# RT_SUPER_B.net
KiCad netlist of a schematic drawn in Altium Designer
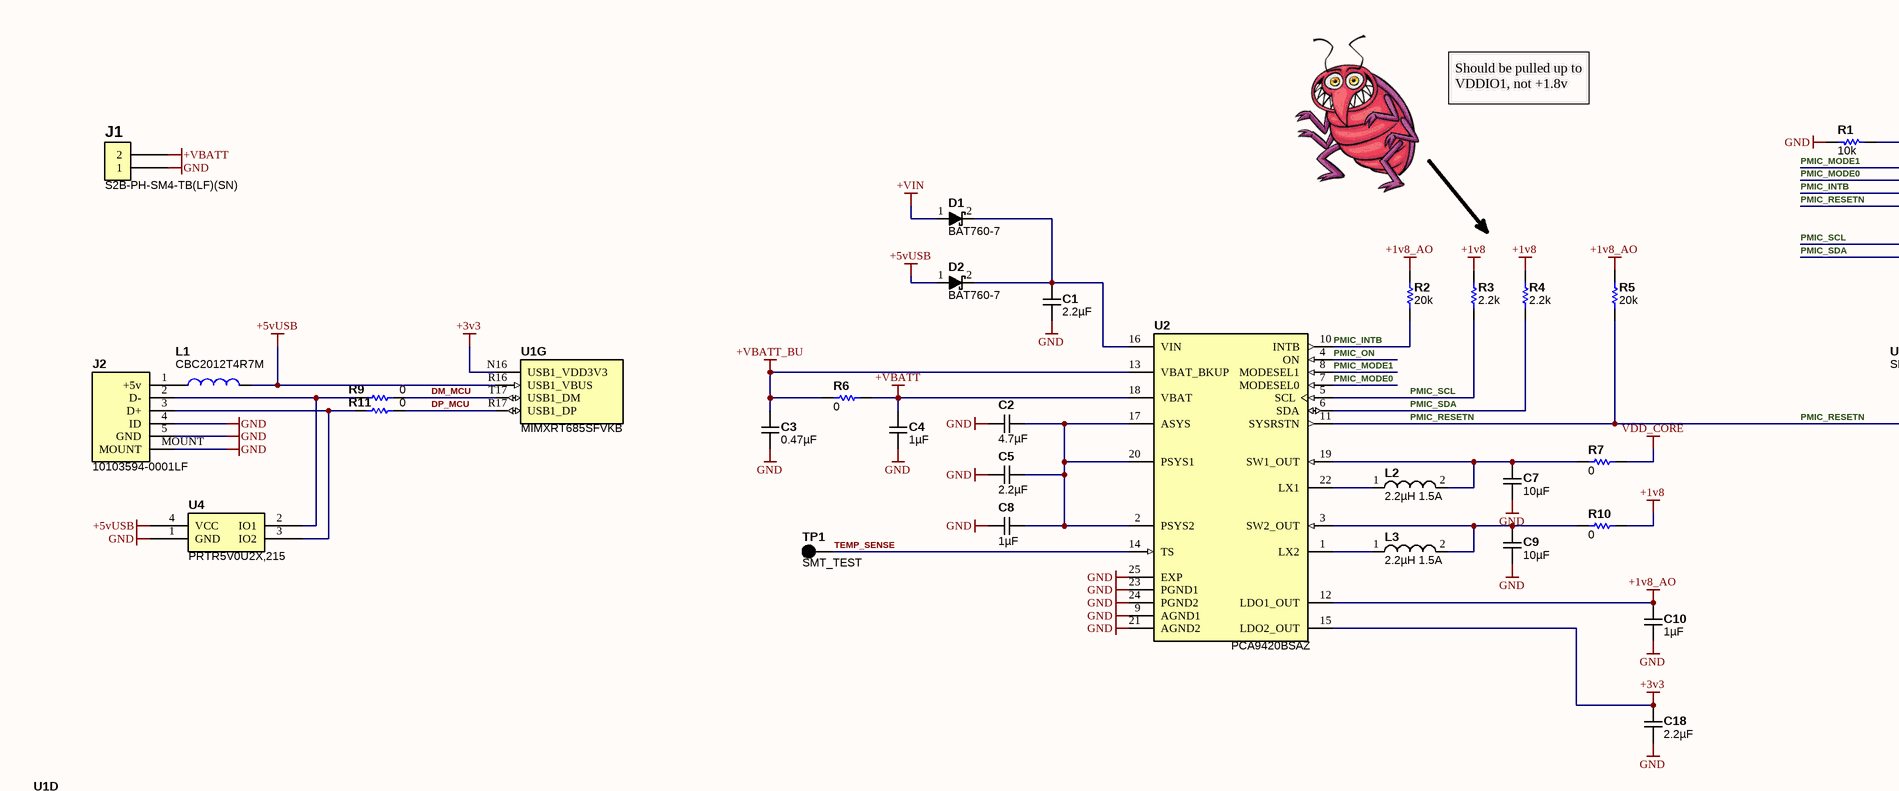
[diagram p0: RT_SUPER_B.SchDoc, top left]
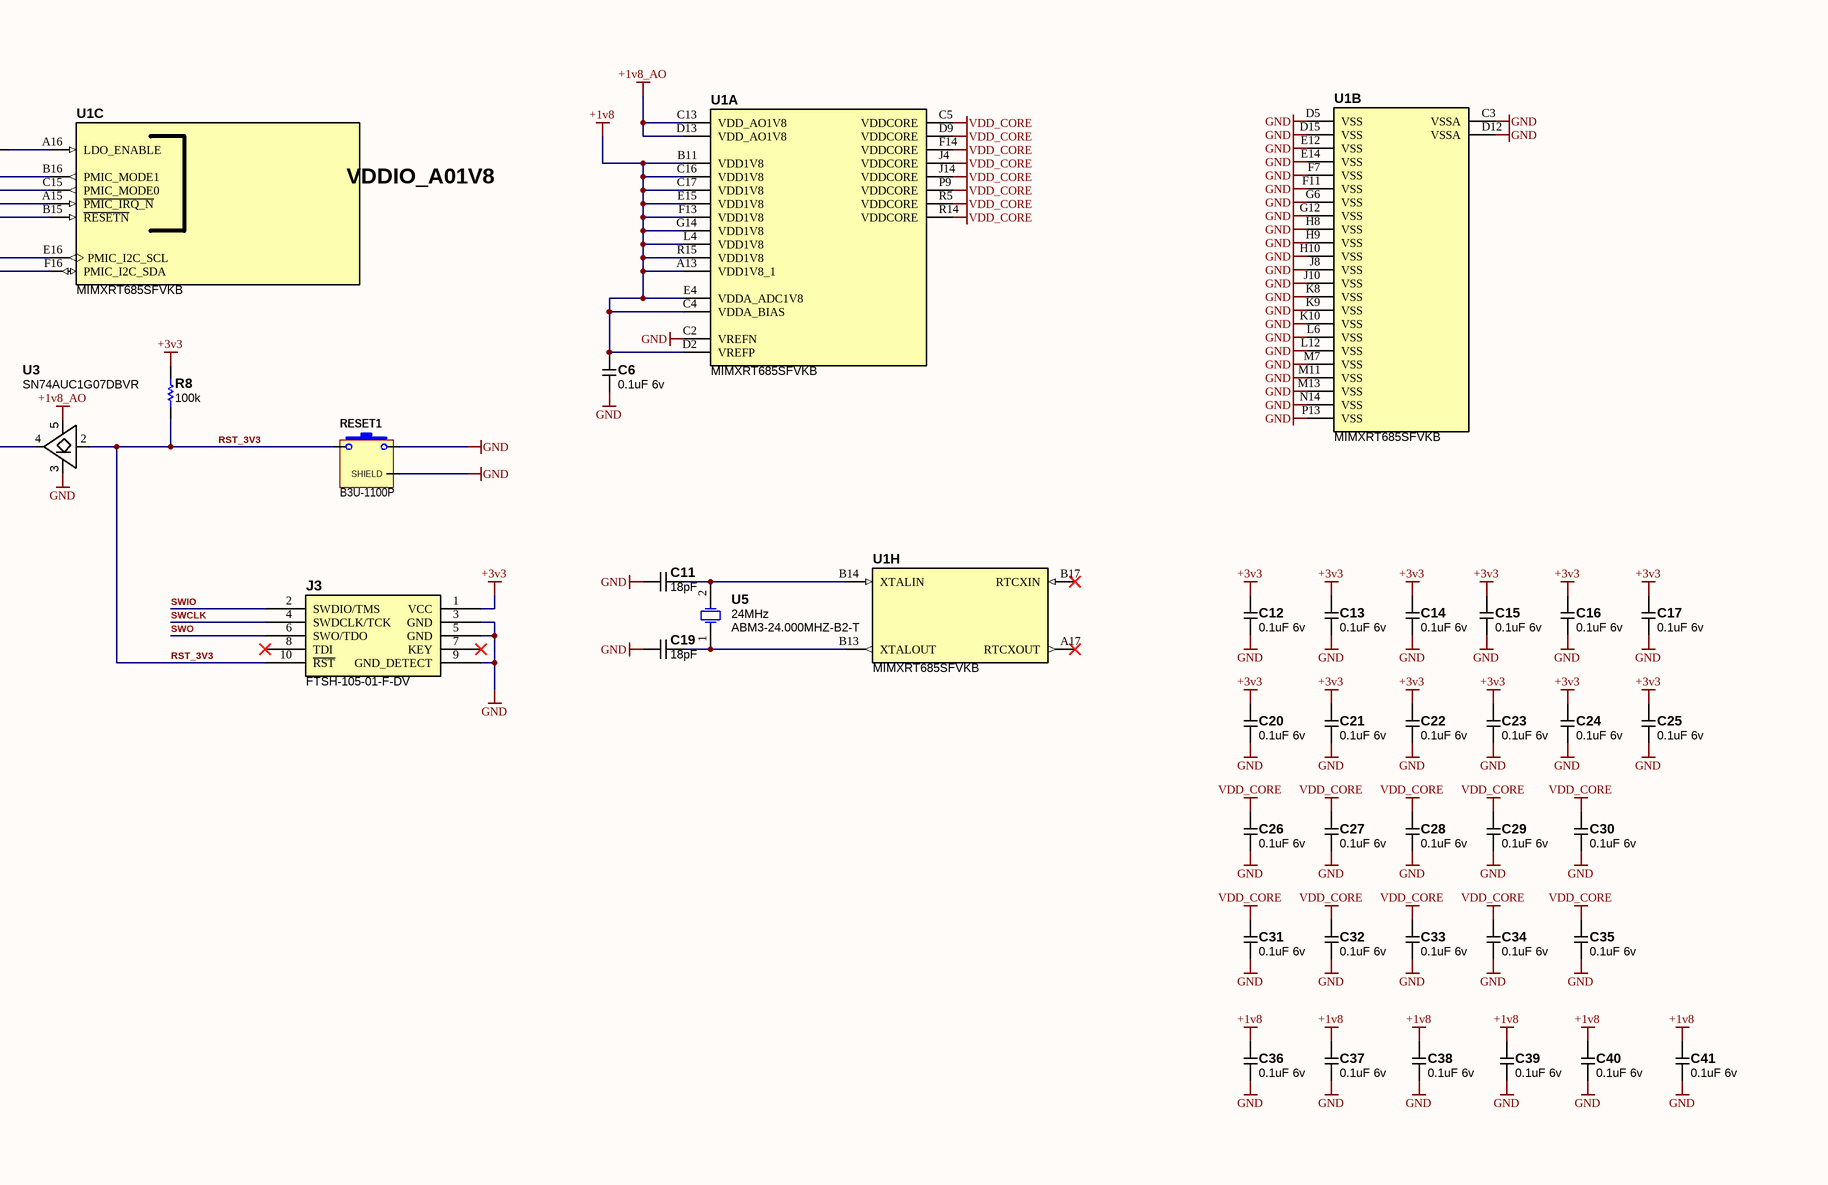
[diagram p1: RT_SUPER_B.SchDoc, top right]
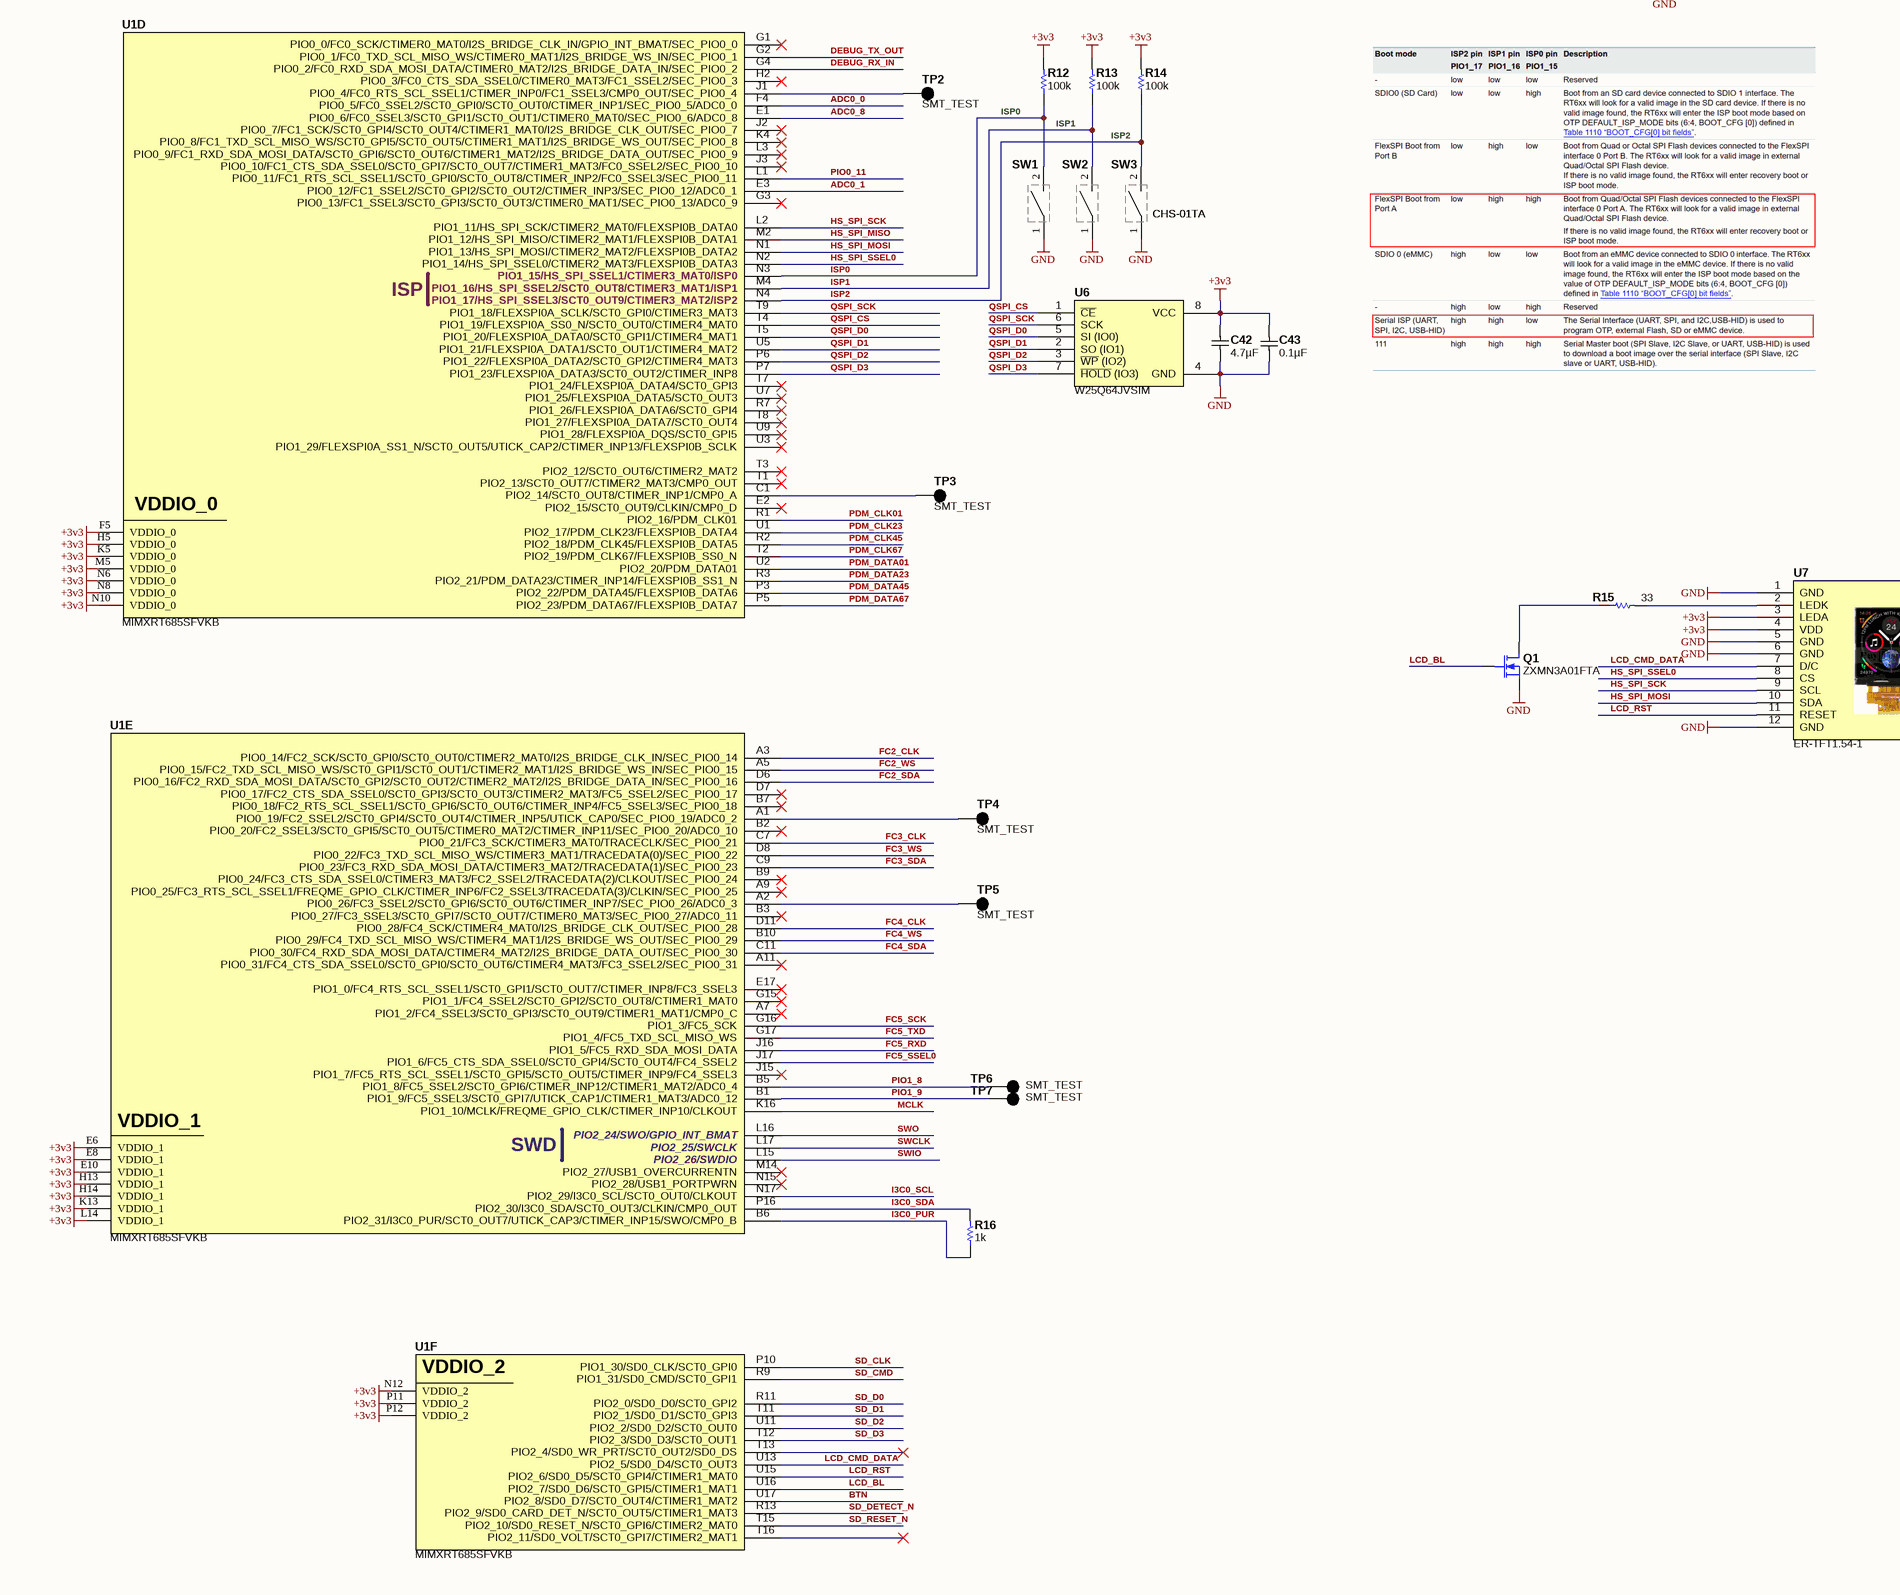
[diagram p2: RT_SUPER_B.SchDoc, bottom left]
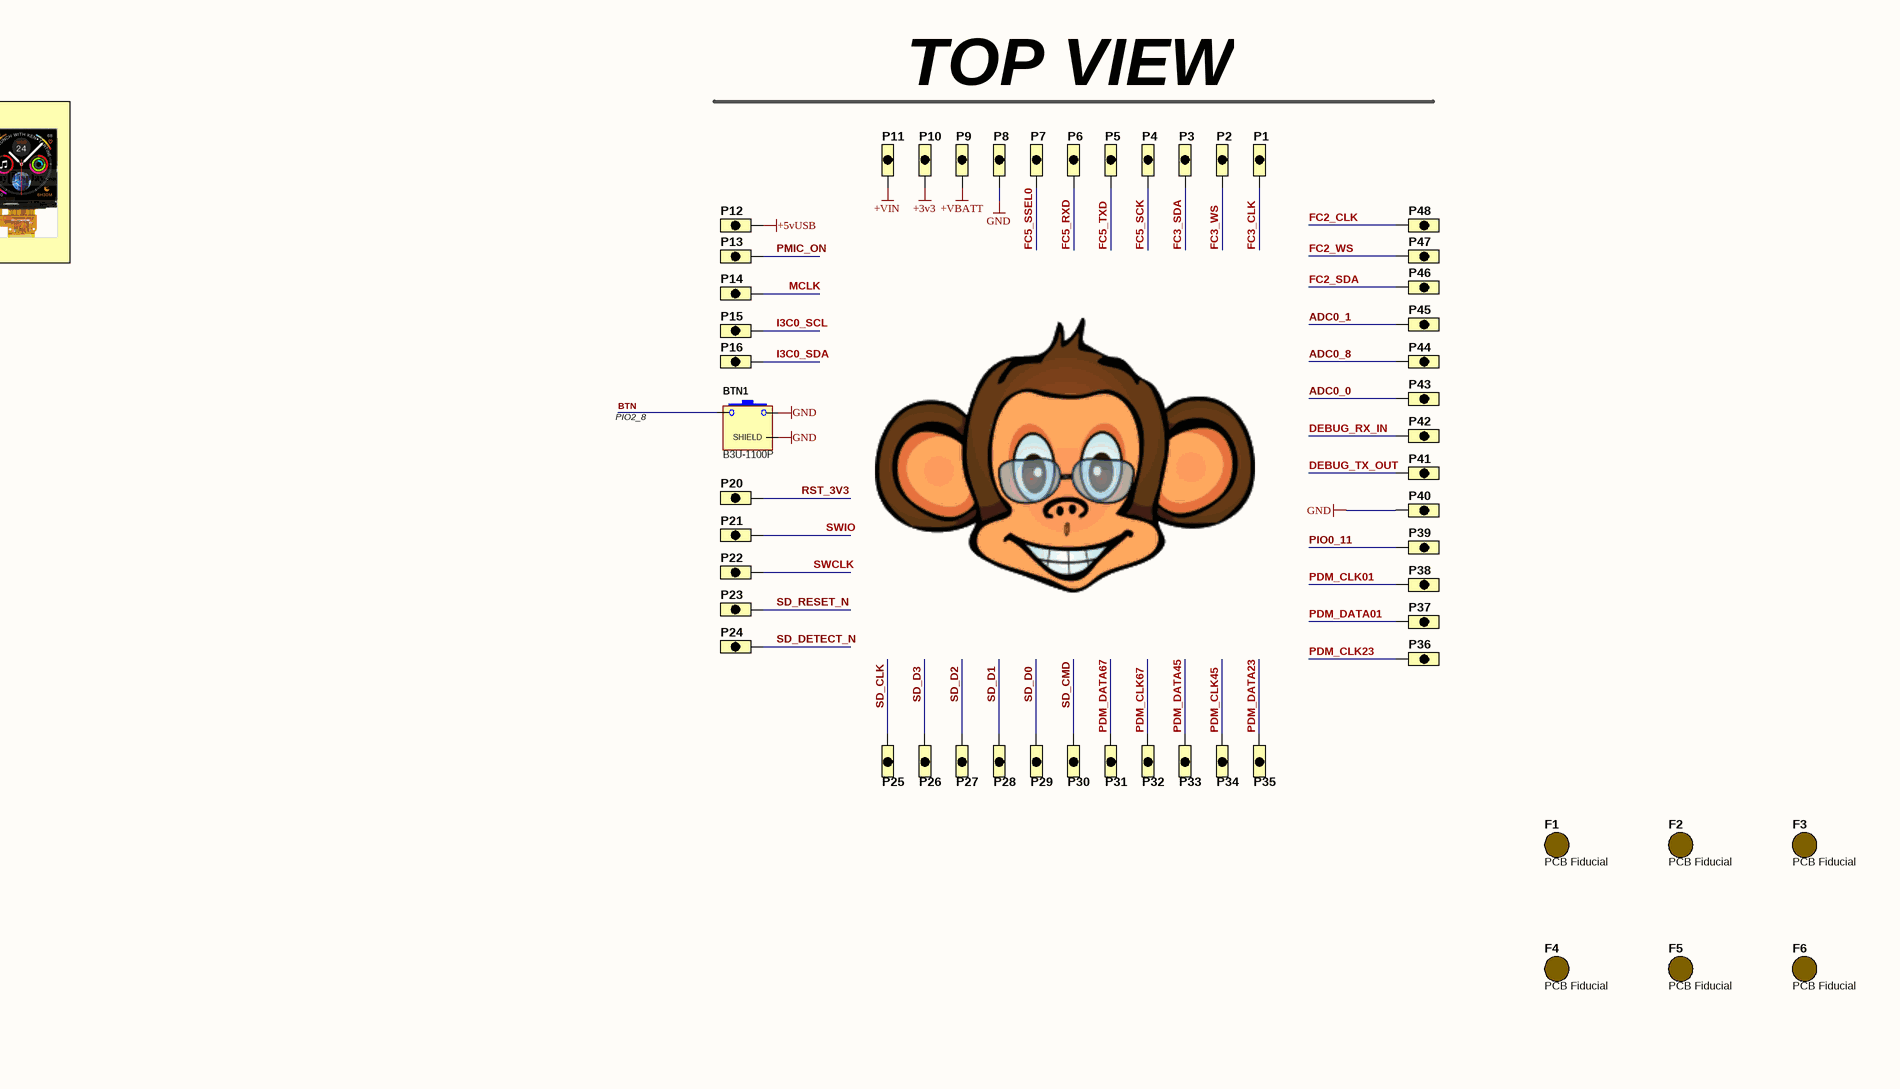
[diagram p3: RT_SUPER_B.SchDoc, bottom right]

(export (version "E")
  (design (tool "Eeschema 10.0.6"))
  (components
    (comp (ref "BTN1")
      (value "B3U-1100P")
      (footprint "OMRON_B3U-1100P")
      (description "SWITCH TACTILE SPST-NO 0.05A 12V")
      (fields (field (name "MANUFACTURER") "Omron Electronics Inc-EMC Div"))
      (libsource (lib "Switches-N") (part "B3U-1100P"))
    )
    (comp (ref "C1")
      (value "2.2µF")
      (footprint "C0603_0.90MM_MD")
      (description "CAP CER 2.2UF 6.3V X7R 0603")
      (fields
        (field (name "MANUFACTURER PART NUMBER") "GCM188R70J225KE22D")
        (field (name "MANUFACTURER") "Murata Electronics")
      )
      (libsource (lib "Capacitors - Murata - AEC-Q200") (part "C_2P_NP"))
    )
    (comp (ref "C2")
      (value "4.7µF")
      (footprint "C0603_1.00MM_MD")
      (description "CAP CER 4.7UF 6.3V X7S 0603")
      (fields
        (field (name "MANUFACTURER PART NUMBER") "GCJ188C70J475KE02D")
        (field (name "MANUFACTURER") "Murata Electronics")
      )
      (libsource (lib "Capacitors - Murata - AEC-Q200") (part "C_2P_NP"))
    )
    (comp (ref "C3")
      (value "0.47µF")
      (footprint "C0402_0.55MM_HD")
      (description "CAP CER 0.47UF 25V X5R 0402")
      (fields
        (field (name "MANUFACTURER PART NUMBER") "GRT155R61E474KE01D")
        (field (name "MANUFACTURER") "Murata Electronics")
      )
      (libsource (lib "Capacitors - Murata - AEC-Q200") (part "C_2P_NP"))
    )
    (comp (ref "C4")
      (value "1µF")
      (footprint "C0402_0.55MM_HD")
      (description "CAP CER 1UF 10V X7S 0402")
      (fields
        (field (name "MANUFACTURER PART NUMBER") "GCM155C71A105KE38D")
        (field (name "MANUFACTURER") "Murata Electronics")
      )
      (libsource (lib "Capacitors - Murata - AEC-Q200") (part "C_2P_NP"))
    )
    (comp (ref "C5")
      (value "2.2µF")
      (footprint "C0603_0.90MM_MD")
      (description "CAP CER 2.2UF 6.3V X7R 0603")
      (fields
        (field (name "MANUFACTURER PART NUMBER") "GCM188R70J225KE22D")
        (field (name "MANUFACTURER") "Murata Electronics")
      )
      (libsource (lib "Capacitors - Murata - AEC-Q200") (part "C_2P_NP"))
    )
    (comp (ref "C6")
      (value "0.1uF 6v")
      (footprint "C0201_PERFECT")
      (description "Cap Ceramic 0.1uF 6.3VDC X5R 10% SMD 0201 Paper T/R")
      (fields
        (field (name "MANUFACTURER PART NUMBER") "CC0201KRX5R5BB104")
        (field (name "MANUFACTURER") "Yageo")
      )
      (libsource (lib "eCapacitors") (part "CC0201KRX5R5BB104"))
    )
    (comp (ref "C7")
      (value "10µF")
      (footprint "C0603_0.90MM_MD")
      (description "CAP CER 10UF 10V X5R 0603")
      (fields
        (field (name "MANUFACTURER PART NUMBER") "GRT188R61A106ME13D")
        (field (name "MANUFACTURER") "Murata Electronics")
      )
      (libsource (lib "Capacitors - Murata - AEC-Q200") (part "C_2P_NP"))
    )
    (comp (ref "C8")
      (value "1µF")
      (footprint "C0402_0.55MM_HD")
      (description "CAP CER 1UF 10V X7S 0402")
      (fields
        (field (name "MANUFACTURER PART NUMBER") "GCM155C71A105KE38D")
        (field (name "MANUFACTURER") "Murata Electronics")
      )
      (libsource (lib "Capacitors - Murata - AEC-Q200") (part "C_2P_NP"))
    )
    (comp (ref "C9")
      (value "10µF")
      (footprint "C0603_0.90MM_MD")
      (description "CAP CER 10UF 10V X5R 0603")
      (fields
        (field (name "MANUFACTURER PART NUMBER") "GRT188R61A106ME13D")
        (field (name "MANUFACTURER") "Murata Electronics")
      )
      (libsource (lib "Capacitors - Murata - AEC-Q200") (part "C_2P_NP"))
    )
    (comp (ref "C10")
      (value "1µF")
      (footprint "C0402_0.55MM_HD")
      (description "CAP CER 1UF 10V X7S 0402")
      (fields
        (field (name "MANUFACTURER PART NUMBER") "GCM155C71A105KE38D")
        (field (name "MANUFACTURER") "Murata Electronics")
      )
      (libsource (lib "Capacitors - Murata - AEC-Q200") (part "C_2P_NP"))
    )
    (comp (ref "C11")
      (value "18pF")
      (footprint "C0402_0.55MM_HD")
      (description "CAP CER 18PF 50V C0G 0402")
      (fields
        (field (name "MANUFACTURER PART NUMBER") "CGA2B2C0G1H180J050BA")
        (field (name "MANUFACTURER") "TDK Corporation")
      )
      (libsource (lib "Capacitors - TDK- AEC-Q200") (part "C_2P_NP"))
    )
    (comp (ref "C12")
      (value "0.1uF 6v")
      (footprint "C0201_PERFECT")
      (description "Cap Ceramic 0.1uF 6.3VDC X5R 10% SMD 0201 Paper T/R")
      (fields
        (field (name "MANUFACTURER PART NUMBER") "CC0201KRX5R5BB104")
        (field (name "MANUFACTURER") "Yageo")
      )
      (libsource (lib "eCapacitors") (part "CC0201KRX5R5BB104"))
    )
    (comp (ref "C13")
      (value "0.1uF 6v")
      (footprint "C0201_PERFECT")
      (description "Cap Ceramic 0.1uF 6.3VDC X5R 10% SMD 0201 Paper T/R")
      (fields
        (field (name "MANUFACTURER PART NUMBER") "CC0201KRX5R5BB104")
        (field (name "MANUFACTURER") "Yageo")
      )
      (libsource (lib "eCapacitors") (part "CC0201KRX5R5BB104"))
    )
    (comp (ref "C14")
      (value "0.1uF 6v")
      (footprint "C0201_PERFECT")
      (description "Cap Ceramic 0.1uF 6.3VDC X5R 10% SMD 0201 Paper T/R")
      (fields
        (field (name "MANUFACTURER PART NUMBER") "CC0201KRX5R5BB104")
        (field (name "MANUFACTURER") "Yageo")
      )
      (libsource (lib "eCapacitors") (part "CC0201KRX5R5BB104"))
    )
    (comp (ref "C15")
      (value "0.1uF 6v")
      (footprint "C0201_PERFECT")
      (description "Cap Ceramic 0.1uF 6.3VDC X5R 10% SMD 0201 Paper T/R")
      (fields
        (field (name "MANUFACTURER PART NUMBER") "CC0201KRX5R5BB104")
        (field (name "MANUFACTURER") "Yageo")
      )
      (libsource (lib "eCapacitors") (part "CC0201KRX5R5BB104"))
    )
    (comp (ref "C16")
      (value "0.1uF 6v")
      (footprint "C0201_PERFECT")
      (description "Cap Ceramic 0.1uF 6.3VDC X5R 10% SMD 0201 Paper T/R")
      (fields
        (field (name "MANUFACTURER PART NUMBER") "CC0201KRX5R5BB104")
        (field (name "MANUFACTURER") "Yageo")
      )
      (libsource (lib "eCapacitors") (part "CC0201KRX5R5BB104"))
    )
    (comp (ref "C17")
      (value "0.1uF 6v")
      (footprint "C0201_PERFECT")
      (description "Cap Ceramic 0.1uF 6.3VDC X5R 10% SMD 0201 Paper T/R")
      (fields
        (field (name "MANUFACTURER PART NUMBER") "CC0201KRX5R5BB104")
        (field (name "MANUFACTURER") "Yageo")
      )
      (libsource (lib "eCapacitors") (part "CC0201KRX5R5BB104"))
    )
    (comp (ref "C18")
      (value "2.2µF")
      (footprint "C0603_0.90MM_MD")
      (description "CAP CER 2.2UF 6.3V X7R 0603")
      (fields
        (field (name "MANUFACTURER PART NUMBER") "GCM188R70J225KE22D")
        (field (name "MANUFACTURER") "Murata Electronics")
      )
      (libsource (lib "Capacitors - Murata - AEC-Q200") (part "C_2P_NP"))
    )
    (comp (ref "C19")
      (value "18pF")
      (footprint "C0402_0.55MM_HD")
      (description "CAP CER 18PF 50V C0G 0402")
      (fields
        (field (name "MANUFACTURER PART NUMBER") "CGA2B2C0G1H180J050BA")
        (field (name "MANUFACTURER") "TDK Corporation")
      )
      (libsource (lib "Capacitors - TDK- AEC-Q200") (part "C_2P_NP"))
    )
    (comp (ref "C20")
      (value "0.1uF 6v")
      (footprint "C0201_PERFECT")
      (description "Cap Ceramic 0.1uF 6.3VDC X5R 10% SMD 0201 Paper T/R")
      (fields
        (field (name "MANUFACTURER PART NUMBER") "CC0201KRX5R5BB104")
        (field (name "MANUFACTURER") "Yageo")
      )
      (libsource (lib "eCapacitors") (part "CC0201KRX5R5BB104"))
    )
    (comp (ref "C21")
      (value "0.1uF 6v")
      (footprint "C0201_PERFECT")
      (description "Cap Ceramic 0.1uF 6.3VDC X5R 10% SMD 0201 Paper T/R")
      (fields
        (field (name "MANUFACTURER PART NUMBER") "CC0201KRX5R5BB104")
        (field (name "MANUFACTURER") "Yageo")
      )
      (libsource (lib "eCapacitors") (part "CC0201KRX5R5BB104"))
    )
    (comp (ref "C22")
      (value "0.1uF 6v")
      (footprint "C0201_PERFECT")
      (description "Cap Ceramic 0.1uF 6.3VDC X5R 10% SMD 0201 Paper T/R")
      (fields
        (field (name "MANUFACTURER PART NUMBER") "CC0201KRX5R5BB104")
        (field (name "MANUFACTURER") "Yageo")
      )
      (libsource (lib "eCapacitors") (part "CC0201KRX5R5BB104"))
    )
    (comp (ref "C23")
      (value "0.1uF 6v")
      (footprint "C0201_PERFECT")
      (description "Cap Ceramic 0.1uF 6.3VDC X5R 10% SMD 0201 Paper T/R")
      (fields
        (field (name "MANUFACTURER PART NUMBER") "CC0201KRX5R5BB104")
        (field (name "MANUFACTURER") "Yageo")
      )
      (libsource (lib "eCapacitors") (part "CC0201KRX5R5BB104"))
    )
    (comp (ref "C24")
      (value "0.1uF 6v")
      (footprint "C0201_PERFECT")
      (description "Cap Ceramic 0.1uF 6.3VDC X5R 10% SMD 0201 Paper T/R")
      (fields
        (field (name "MANUFACTURER PART NUMBER") "CC0201KRX5R5BB104")
        (field (name "MANUFACTURER") "Yageo")
      )
      (libsource (lib "eCapacitors") (part "CC0201KRX5R5BB104"))
    )
    (comp (ref "C25")
      (value "0.1uF 6v")
      (footprint "C0201_PERFECT")
      (description "Cap Ceramic 0.1uF 6.3VDC X5R 10% SMD 0201 Paper T/R")
      (fields
        (field (name "MANUFACTURER PART NUMBER") "CC0201KRX5R5BB104")
        (field (name "MANUFACTURER") "Yageo")
      )
      (libsource (lib "eCapacitors") (part "CC0201KRX5R5BB104"))
    )
    (comp (ref "C26")
      (value "0.1uF 6v")
      (footprint "C0201_PERFECT")
      (description "Cap Ceramic 0.1uF 6.3VDC X5R 10% SMD 0201 Paper T/R")
      (fields
        (field (name "MANUFACTURER PART NUMBER") "CC0201KRX5R5BB104")
        (field (name "MANUFACTURER") "Yageo")
      )
      (libsource (lib "eCapacitors") (part "CC0201KRX5R5BB104"))
    )
    (comp (ref "C27")
      (value "0.1uF 6v")
      (footprint "C0201_PERFECT")
      (description "Cap Ceramic 0.1uF 6.3VDC X5R 10% SMD 0201 Paper T/R")
      (fields
        (field (name "MANUFACTURER PART NUMBER") "CC0201KRX5R5BB104")
        (field (name "MANUFACTURER") "Yageo")
      )
      (libsource (lib "eCapacitors") (part "CC0201KRX5R5BB104"))
    )
    (comp (ref "C28")
      (value "0.1uF 6v")
      (footprint "C0201_PERFECT")
      (description "Cap Ceramic 0.1uF 6.3VDC X5R 10% SMD 0201 Paper T/R")
      (fields
        (field (name "MANUFACTURER PART NUMBER") "CC0201KRX5R5BB104")
        (field (name "MANUFACTURER") "Yageo")
      )
      (libsource (lib "eCapacitors") (part "CC0201KRX5R5BB104"))
    )
    (comp (ref "C29")
      (value "0.1uF 6v")
      (footprint "C0201_PERFECT")
      (description "Cap Ceramic 0.1uF 6.3VDC X5R 10% SMD 0201 Paper T/R")
      (fields
        (field (name "MANUFACTURER PART NUMBER") "CC0201KRX5R5BB104")
        (field (name "MANUFACTURER") "Yageo")
      )
      (libsource (lib "eCapacitors") (part "CC0201KRX5R5BB104"))
    )
    (comp (ref "C30")
      (value "0.1uF 6v")
      (footprint "C0201_PERFECT")
      (description "Cap Ceramic 0.1uF 6.3VDC X5R 10% SMD 0201 Paper T/R")
      (fields
        (field (name "MANUFACTURER PART NUMBER") "CC0201KRX5R5BB104")
        (field (name "MANUFACTURER") "Yageo")
      )
      (libsource (lib "eCapacitors") (part "CC0201KRX5R5BB104"))
    )
    (comp (ref "C31")
      (value "0.1uF 6v")
      (footprint "C0201_PERFECT")
      (description "Cap Ceramic 0.1uF 6.3VDC X5R 10% SMD 0201 Paper T/R")
      (fields
        (field (name "MANUFACTURER PART NUMBER") "CC0201KRX5R5BB104")
        (field (name "MANUFACTURER") "Yageo")
      )
      (libsource (lib "eCapacitors") (part "CC0201KRX5R5BB104"))
    )
    (comp (ref "C32")
      (value "0.1uF 6v")
      (footprint "C0201_PERFECT")
      (description "Cap Ceramic 0.1uF 6.3VDC X5R 10% SMD 0201 Paper T/R")
      (fields
        (field (name "MANUFACTURER PART NUMBER") "CC0201KRX5R5BB104")
        (field (name "MANUFACTURER") "Yageo")
      )
      (libsource (lib "eCapacitors") (part "CC0201KRX5R5BB104"))
    )
    (comp (ref "C33")
      (value "0.1uF 6v")
      (footprint "C0201_PERFECT")
      (description "Cap Ceramic 0.1uF 6.3VDC X5R 10% SMD 0201 Paper T/R")
      (fields
        (field (name "MANUFACTURER PART NUMBER") "CC0201KRX5R5BB104")
        (field (name "MANUFACTURER") "Yageo")
      )
      (libsource (lib "eCapacitors") (part "CC0201KRX5R5BB104"))
    )
    (comp (ref "C34")
      (value "0.1uF 6v")
      (footprint "C0201_PERFECT")
      (description "Cap Ceramic 0.1uF 6.3VDC X5R 10% SMD 0201 Paper T/R")
      (fields
        (field (name "MANUFACTURER PART NUMBER") "CC0201KRX5R5BB104")
        (field (name "MANUFACTURER") "Yageo")
      )
      (libsource (lib "eCapacitors") (part "CC0201KRX5R5BB104"))
    )
    (comp (ref "C35")
      (value "0.1uF 6v")
      (footprint "C0201_PERFECT")
      (description "Cap Ceramic 0.1uF 6.3VDC X5R 10% SMD 0201 Paper T/R")
      (fields
        (field (name "MANUFACTURER PART NUMBER") "CC0201KRX5R5BB104")
        (field (name "MANUFACTURER") "Yageo")
      )
      (libsource (lib "eCapacitors") (part "CC0201KRX5R5BB104"))
    )
    (comp (ref "C36")
      (value "0.1uF 6v")
      (footprint "C0201_PERFECT")
      (description "Cap Ceramic 0.1uF 6.3VDC X5R 10% SMD 0201 Paper T/R")
      (fields
        (field (name "MANUFACTURER PART NUMBER") "CC0201KRX5R5BB104")
        (field (name "MANUFACTURER") "Yageo")
      )
      (libsource (lib "eCapacitors") (part "CC0201KRX5R5BB104"))
    )
    (comp (ref "C37")
      (value "0.1uF 6v")
      (footprint "C0201_PERFECT")
      (description "Cap Ceramic 0.1uF 6.3VDC X5R 10% SMD 0201 Paper T/R")
      (fields
        (field (name "MANUFACTURER PART NUMBER") "CC0201KRX5R5BB104")
        (field (name "MANUFACTURER") "Yageo")
      )
      (libsource (lib "eCapacitors") (part "CC0201KRX5R5BB104"))
    )
    (comp (ref "C38")
      (value "0.1uF 6v")
      (footprint "C0201_PERFECT")
      (description "Cap Ceramic 0.1uF 6.3VDC X5R 10% SMD 0201 Paper T/R")
      (fields
        (field (name "MANUFACTURER PART NUMBER") "CC0201KRX5R5BB104")
        (field (name "MANUFACTURER") "Yageo")
      )
      (libsource (lib "eCapacitors") (part "CC0201KRX5R5BB104"))
    )
    (comp (ref "C39")
      (value "0.1uF 6v")
      (footprint "C0201_PERFECT")
      (description "Cap Ceramic 0.1uF 6.3VDC X5R 10% SMD 0201 Paper T/R")
      (fields
        (field (name "MANUFACTURER PART NUMBER") "CC0201KRX5R5BB104")
        (field (name "MANUFACTURER") "Yageo")
      )
      (libsource (lib "eCapacitors") (part "CC0201KRX5R5BB104"))
    )
    (comp (ref "C40")
      (value "0.1uF 6v")
      (footprint "C0201_PERFECT")
      (description "Cap Ceramic 0.1uF 6.3VDC X5R 10% SMD 0201 Paper T/R")
      (fields
        (field (name "MANUFACTURER PART NUMBER") "CC0201KRX5R5BB104")
        (field (name "MANUFACTURER") "Yageo")
      )
      (libsource (lib "eCapacitors") (part "CC0201KRX5R5BB104"))
    )
    (comp (ref "C41")
      (value "0.1uF 6v")
      (footprint "C0201_PERFECT")
      (description "Cap Ceramic 0.1uF 6.3VDC X5R 10% SMD 0201 Paper T/R")
      (fields
        (field (name "MANUFACTURER PART NUMBER") "CC0201KRX5R5BB104")
        (field (name "MANUFACTURER") "Yageo")
      )
      (libsource (lib "eCapacitors") (part "CC0201KRX5R5BB104"))
    )
    (comp (ref "C42")
      (value "4.7µF")
      (footprint "C0805_1.45MM_MD")
      (description "CAP CER 4.7UF 10V X7R 0805")
      (fields
        (field (name "MANUFACTURER PART NUMBER") "CGA4J3X7R1A475K125AB")
        (field (name "MANUFACTURER") "TDK Corporation")
      )
      (libsource (lib "Capacitors - TDK- AEC-Q200") (part "C_2P_NP"))
    )
    (comp (ref "C43")
      (value "0.1µF")
      (footprint "C0402_0.55MM_MD")
      (description "CAP CER 0.1UF 16V X7R 0402")
      (fields
        (field (name "MANUFACTURER PART NUMBER") "CGA2B1X7R1C104K050BC")
        (field (name "MANUFACTURER") "TDK Corporation")
      )
      (libsource (lib "Capacitors - TDK- AEC-Q200") (part "C_2P_NP"))
    )
    (comp (ref "D1")
      (value "BAT760-7")
      (footprint "D_SOD-323_P")
      (description "DIODE SCHOTTKY 30V 1A SOD323")
      (fields (field (name "MANUFACTURER") "Diodes Inc"))
      (libsource (lib "Diodes") (part "DS_1A_2C"))
    )
    (comp (ref "D2")
      (value "BAT760-7")
      (footprint "D_SOD-323_P")
      (description "DIODE SCHOTTKY 30V 1A SOD323")
      (fields (field (name "MANUFACTURER") "Diodes Inc"))
      (libsource (lib "Diodes") (part "DS_1A_2C"))
    )
    (comp (ref "F1")
      (value "PCB Fiducial")
      (footprint "Fiducial 1mm - 2mm")
      (libsource (lib "eFiducial") (part "Fiducial"))
    )
    (comp (ref "F2")
      (value "PCB Fiducial")
      (footprint "Fiducial 1mm - 2mm")
      (libsource (lib "eFiducial") (part "Fiducial"))
    )
    (comp (ref "F3")
      (value "PCB Fiducial")
      (footprint "Fiducial 1mm - 2mm")
      (libsource (lib "eFiducial") (part "Fiducial"))
    )
    (comp (ref "F4")
      (value "PCB Fiducial")
      (footprint "Fiducial 1mm - 2mm")
      (libsource (lib "eFiducial") (part "Fiducial"))
    )
    (comp (ref "F5")
      (value "PCB Fiducial")
      (footprint "Fiducial 1mm - 2mm")
      (libsource (lib "eFiducial") (part "Fiducial"))
    )
    (comp (ref "F6")
      (value "PCB Fiducial")
      (footprint "Fiducial 1mm - 2mm")
      (libsource (lib "eFiducial") (part "Fiducial"))
    )
    (comp (ref "J1")
      (value "S2B-PH-SM4-TB(LF)(SN)")
      (footprint "S2B-PH-SM4-TB(LF)(SN)")
      (description "CONN HEADER PH SIDE 2POS 2MM SMD")
      (fields (field (name "MANUFACTURER") "JST Sales America Inc"))
      (libsource (lib "eConnector_JST_PH") (part "S2B-PH-SM4-TB(LF)(SN)"))
    )
    (comp (ref "J2")
      (value "10103594-0001LF")
      (footprint "10103594-0001LF")
      (description "CONN RCPT STD MICRO USB TYPE B")
      (fields (field (name "MANUFACTURER") "FCI"))
      (libsource (lib "eConnector_USB") (part "10103594-0001LF"))
    )
    (comp (ref "J3")
      (value "FTSH-105-01-F-DV")
      (footprint "FTSH-105-01-F-DV-K-A")
      (description "SAMTEC - FTSH-105-01-F-DV - .050 X .050")
      (fields (field (name "MANUFACTURER") "SAMTEC"))
      (libsource (lib "eConnector") (part "CORTEX-DEBUG"))
    )
    (comp (ref "L1")
      (value "CBC2012T4R7M")
      (footprint "C0805_1.45MM_MD")
      (description "FIXED IND 4.7UH 520MA 650 MOHM")
      (fields (field (name "MANUFACTURER") "Taiyo Yuden") (field (name "TOLERANCE") "20%"))
      (libsource (lib "eInductor") (part "CBC2012T4R7M"))
    )
    (comp (ref "L2")
      (value "2.2µH 1.5A")
      (footprint "L_NRH3012")
      (description "Inductor 2.2µH 1.5A")
      (fields
        (field (name "MANUFACTURER PART NUMBER") "NRH3012T2R2MN")
        (field (name "MANUFACTURER") "Taiyo Yuden")
      )
      (libsource (lib "Inductors") (part "L_2P"))
    )
    (comp (ref "L3")
      (value "2.2µH 1.5A")
      (footprint "L_NRH3012")
      (description "Inductor 2.2µH 1.5A")
      (fields
        (field (name "MANUFACTURER PART NUMBER") "NRH3012T2R2MN")
        (field (name "MANUFACTURER") "Taiyo Yuden")
      )
      (libsource (lib "Inductors") (part "L_2P"))
    )
    (comp (ref "P1")
      (value "~")
      (footprint "CASTELLATED")
      (libsource (lib "eConnector") (part "CASTELLATED"))
    )
    (comp (ref "P2")
      (value "~")
      (footprint "CASTELLATED")
      (libsource (lib "eConnector") (part "CASTELLATED"))
    )
    (comp (ref "P3")
      (value "~")
      (footprint "CASTELLATED")
      (libsource (lib "eConnector") (part "CASTELLATED"))
    )
    (comp (ref "P4")
      (value "~")
      (footprint "CASTELLATED")
      (libsource (lib "eConnector") (part "CASTELLATED"))
    )
    (comp (ref "P5")
      (value "~")
      (footprint "CASTELLATED")
      (libsource (lib "eConnector") (part "CASTELLATED"))
    )
    (comp (ref "P6")
      (value "~")
      (footprint "CASTELLATED")
      (libsource (lib "eConnector") (part "CASTELLATED"))
    )
    (comp (ref "P7")
      (value "~")
      (footprint "CASTELLATED")
      (libsource (lib "eConnector") (part "CASTELLATED"))
    )
    (comp (ref "P8")
      (value "~")
      (footprint "CASTELLATED")
      (libsource (lib "eConnector") (part "CASTELLATED"))
    )
    (comp (ref "P9")
      (value "~")
      (footprint "CASTELLATED")
      (libsource (lib "eConnector") (part "CASTELLATED"))
    )
    (comp (ref "P10")
      (value "~")
      (footprint "CASTELLATED")
      (libsource (lib "eConnector") (part "CASTELLATED"))
    )
    (comp (ref "P11")
      (value "~")
      (footprint "CASTELLATED")
      (libsource (lib "eConnector") (part "CASTELLATED"))
    )
    (comp (ref "P12") (value "~") (footprint "CASTELLATED") (libsource (lib "") (part "CASTELLATED_2")))
    (comp (ref "P13") (value "~") (footprint "CASTELLATED") (libsource (lib "") (part "CASTELLATED_1")))
    (comp (ref "P14") (value "~") (footprint "CASTELLATED") (libsource (lib "") (part "CASTELLATED_1")))
    (comp (ref "P15") (value "~") (footprint "CASTELLATED") (libsource (lib "") (part "CASTELLATED_1")))
    (comp (ref "P16") (value "~") (footprint "CASTELLATED") (libsource (lib "") (part "CASTELLATED_1")))
    (comp (ref "P20") (value "~") (footprint "CASTELLATED") (libsource (lib "") (part "CASTELLATED_1")))
    (comp (ref "P21") (value "~") (footprint "CASTELLATED") (libsource (lib "") (part "CASTELLATED_1")))
    (comp (ref "P22") (value "~") (footprint "CASTELLATED") (libsource (lib "") (part "CASTELLATED_1")))
    (comp (ref "P23") (value "~") (footprint "CASTELLATED") (libsource (lib "") (part "CASTELLATED_1")))
    (comp (ref "P24") (value "~") (footprint "CASTELLATED") (libsource (lib "") (part "CASTELLATED_2")))
    (comp (ref "P25") (value "~") (footprint "CASTELLATED") (libsource (lib "") (part "CASTELLATED_2")))
    (comp (ref "P26") (value "~") (footprint "CASTELLATED") (libsource (lib "") (part "CASTELLATED_2")))
    (comp (ref "P27") (value "~") (footprint "CASTELLATED") (libsource (lib "") (part "CASTELLATED_2")))
    (comp (ref "P28") (value "~") (footprint "CASTELLATED") (libsource (lib "") (part "CASTELLATED_2")))
    (comp (ref "P29") (value "~") (footprint "CASTELLATED") (libsource (lib "") (part "CASTELLATED_2")))
    (comp (ref "P30") (value "~") (footprint "CASTELLATED") (libsource (lib "") (part "CASTELLATED_2")))
    (comp (ref "P31") (value "~") (footprint "CASTELLATED") (libsource (lib "") (part "CASTELLATED_2")))
    (comp (ref "P32") (value "~") (footprint "CASTELLATED") (libsource (lib "") (part "CASTELLATED_2")))
    (comp (ref "P33") (value "~") (footprint "CASTELLATED") (libsource (lib "") (part "CASTELLATED_2")))
    (comp (ref "P34") (value "~") (footprint "CASTELLATED") (libsource (lib "") (part "CASTELLATED_2")))
    (comp (ref "P35") (value "~") (footprint "CASTELLATED") (libsource (lib "") (part "CASTELLATED_2")))
    (comp (ref "P36")
      (value "~")
      (footprint "CASTELLATED")
      (libsource (lib "eConnector") (part "CASTELLATED"))
    )
    (comp (ref "P37")
      (value "~")
      (footprint "CASTELLATED")
      (libsource (lib "eConnector") (part "CASTELLATED"))
    )
    (comp (ref "P38")
      (value "~")
      (footprint "CASTELLATED")
      (libsource (lib "eConnector") (part "CASTELLATED"))
    )
    (comp (ref "P39")
      (value "~")
      (footprint "CASTELLATED")
      (libsource (lib "eConnector") (part "CASTELLATED"))
    )
    (comp (ref "P40")
      (value "~")
      (footprint "CASTELLATED")
      (libsource (lib "eConnector") (part "CASTELLATED"))
    )
    (comp (ref "P41")
      (value "~")
      (footprint "CASTELLATED")
      (libsource (lib "eConnector") (part "CASTELLATED"))
    )
    (comp (ref "P42")
      (value "~")
      (footprint "CASTELLATED")
      (libsource (lib "eConnector") (part "CASTELLATED"))
    )
    (comp (ref "P43")
      (value "~")
      (footprint "CASTELLATED")
      (libsource (lib "eConnector") (part "CASTELLATED"))
    )
    (comp (ref "P44")
      (value "~")
      (footprint "CASTELLATED")
      (libsource (lib "eConnector") (part "CASTELLATED"))
    )
    (comp (ref "P45")
      (value "~")
      (footprint "CASTELLATED")
      (libsource (lib "eConnector") (part "CASTELLATED"))
    )
    (comp (ref "P46")
      (value "~")
      (footprint "CASTELLATED")
      (libsource (lib "eConnector") (part "CASTELLATED"))
    )
    (comp (ref "P47")
      (value "~")
      (footprint "CASTELLATED")
      (libsource (lib "eConnector") (part "CASTELLATED"))
    )
    (comp (ref "P48")
      (value "~")
      (footprint "CASTELLATED")
      (libsource (lib "eConnector") (part "CASTELLATED"))
    )
    (comp (ref "Q1")
      (value "ZXMN3A01FTA")
      (footprint "SOT-23")
      (description "MOSFET N-CH 30V 1.8A SOT23-3")
      (fields (field (name "MANUFACTURER") "Diodes/Zetex"))
      (libsource (lib "eTransistor") (part "ZXMN3A01FTA"))
    )
    (comp (ref "R1")
      (value "10k")
      (footprint "R0402_0.40MM_HD")
      (description "RES 10K OHM 1/10W 1% 0402 SMD")
      (fields
        (field (name "MANUFACTURER PART NUMBER") "ERJ-2RKF1002X")
        (field (name "MANUFACTURER") "Panasonic Electronic Components")
      )
      (libsource (lib "Resistors - Panasonic - AEC-Q200") (part "R_2P"))
    )
    (comp (ref "R2")
      (value "20k")
      (footprint "R0402_0.40MM_HD")
      (description "RES 20K OHM 1/10W 1% 0402 SMD")
      (fields
        (field (name "MANUFACTURER PART NUMBER") "ERJ-2RKF2002X")
        (field (name "MANUFACTURER") "Panasonic Electronic Components")
      )
      (libsource (lib "Resistors - Panasonic - AEC-Q200") (part "R_2P"))
    )
    (comp (ref "R3")
      (value "2.2k")
      (footprint "R0402_0.40MM_HD")
      (description "RES 2.2K OHM 1/10W 1% 0402 SMD")
      (fields
        (field (name "MANUFACTURER PART NUMBER") "ERJ-2RKF2201X")
        (field (name "MANUFACTURER") "Panasonic Electronic Components")
      )
      (libsource (lib "Resistors - Panasonic - AEC-Q200") (part "R_2P"))
    )
    (comp (ref "R4")
      (value "2.2k")
      (footprint "R0402_0.40MM_HD")
      (description "RES 2.2K OHM 1/10W 1% 0402 SMD")
      (fields
        (field (name "MANUFACTURER PART NUMBER") "ERJ-2RKF2201X")
        (field (name "MANUFACTURER") "Panasonic Electronic Components")
      )
      (libsource (lib "Resistors - Panasonic - AEC-Q200") (part "R_2P"))
    )
    (comp (ref "R5")
      (value "20k")
      (footprint "R0402_0.40MM_HD")
      (description "RES 20K OHM 1/10W 1% 0402 SMD")
      (fields
        (field (name "MANUFACTURER PART NUMBER") "ERJ-2RKF2002X")
        (field (name "MANUFACTURER") "Panasonic Electronic Components")
      )
      (libsource (lib "Resistors - Panasonic - AEC-Q200") (part "R_2P"))
    )
    (comp (ref "R6")
      (value "0")
      (footprint "R0402_0.40MM_HD")
      (description "RES 0.0 OHM 1/10W JUMP 0402 SMD")
      (fields
        (field (name "MANUFACTURER PART NUMBER") "ERJ-2GE0R00X")
        (field (name "MANUFACTURER") "Panasonic Electronic Components")
      )
      (libsource (lib "Resistors - Panasonic - AEC-Q200") (part "R_2P"))
    )
    (comp (ref "R7")
      (value "0")
      (footprint "R0402_0.40MM_HD")
      (description "RES 0.0 OHM 1/10W JUMP 0402 SMD")
      (fields
        (field (name "MANUFACTURER PART NUMBER") "ERJ-2GE0R00X")
        (field (name "MANUFACTURER") "Panasonic Electronic Components")
      )
      (libsource (lib "Resistors - Panasonic - AEC-Q200") (part "R_2P"))
    )
    (comp (ref "R8")
      (value "100k")
      (footprint "R0402_0.40MM_HD")
      (description "RES 100K OHM 1/10W 1% 0402 SMD")
      (fields
        (field (name "MANUFACTURER PART NUMBER") "ERJ-2RKF1003X")
        (field (name "MANUFACTURER") "Panasonic Electronic Components")
      )
      (libsource (lib "Resistors - Panasonic - AEC-Q200") (part "R_2P"))
    )
    (comp (ref "R9")
      (value "0")
      (footprint "R0402_0.40MM_MD")
      (description "RES 0.0 OHM 1/10W JUMP 0402 SMD")
      (fields
        (field (name "MANUFACTURER PART NUMBER") "ERJ-2GE0R00X")
        (field (name "MANUFACTURER") "Panasonic Electronic Components")
      )
      (libsource (lib "Resistors - Panasonic - AEC-Q200") (part "R_2P"))
    )
    (comp (ref "R10")
      (value "0")
      (footprint "R0402_0.40MM_HD")
      (description "RES 0.0 OHM 1/10W JUMP 0402 SMD")
      (fields
        (field (name "MANUFACTURER PART NUMBER") "ERJ-2GE0R00X")
        (field (name "MANUFACTURER") "Panasonic Electronic Components")
      )
      (libsource (lib "Resistors - Panasonic - AEC-Q200") (part "R_2P"))
    )
    (comp (ref "R11")
      (value "0")
      (footprint "R0402_0.40MM_MD")
      (description "RES 0.0 OHM 1/10W JUMP 0402 SMD")
      (fields
        (field (name "MANUFACTURER PART NUMBER") "ERJ-2GE0R00X")
        (field (name "MANUFACTURER") "Panasonic Electronic Components")
      )
      (libsource (lib "Resistors - Panasonic - AEC-Q200") (part "R_2P"))
    )
    (comp (ref "R12")
      (value "100k")
      (footprint "R0402_0.40MM_HD")
      (description "RES 100K OHM 1/10W 1% 0402 SMD")
      (fields
        (field (name "MANUFACTURER PART NUMBER") "ERJ-2RKF1003X")
        (field (name "MANUFACTURER") "Panasonic Electronic Components")
      )
      (libsource (lib "Resistors - Panasonic - AEC-Q200") (part "R_2P"))
    )
    (comp (ref "R13")
      (value "100k")
      (footprint "R0402_0.40MM_HD")
      (description "RES 100K OHM 1/10W 1% 0402 SMD")
      (fields
        (field (name "MANUFACTURER PART NUMBER") "ERJ-2RKF1003X")
        (field (name "MANUFACTURER") "Panasonic Electronic Components")
      )
      (libsource (lib "Resistors - Panasonic - AEC-Q200") (part "R_2P"))
    )
    (comp (ref "R14")
      (value "100k")
      (footprint "R0402_0.40MM_HD")
      (description "RES 100K OHM 1/10W 1% 0402 SMD")
      (fields
        (field (name "MANUFACTURER PART NUMBER") "ERJ-2RKF1003X")
        (field (name "MANUFACTURER") "Panasonic Electronic Components")
      )
      (libsource (lib "Resistors - Panasonic - AEC-Q200") (part "R_2P"))
    )
    (comp (ref "R15")
      (value "33")
      (footprint "R0402_0.40MM_HD")
      (description "RES 33 OHM 1/10W 1% 0402 SMD")
      (fields
        (field (name "MANUFACTURER PART NUMBER") "ERJ-2RKF33R0X")
        (field (name "MANUFACTURER") "Panasonic Electronic Components")
      )
      (libsource (lib "Resistors - Panasonic - AEC-Q200") (part "R_2P"))
    )
    (comp (ref "R16")
      (value "1k")
      (footprint "R0402_0.40MM_HD")
      (description "RES 1K OHM 1/10W 1% 0402 SMD")
      (fields
        (field (name "MANUFACTURER PART NUMBER") "ERJ-2RKF1001X")
        (field (name "MANUFACTURER") "Panasonic Electronic Components")
      )
      (libsource (lib "Resistors - Panasonic - AEC-Q200") (part "R_2P"))
    )
    (comp (ref "RESET1")
      (value "B3U-1100P")
      (footprint "OMRON_B3U-1100P")
      (description "SWITCH TACTILE SPST-NO 0.05A 12V")
      (fields (field (name "MANUFACTURER") "Omron Electronics Inc-EMC Div"))
      (libsource (lib "Switches-N") (part "B3U-1100P"))
    )
    (comp (ref "SW1")
      (value "CHS-01TA")
      (footprint "CHS-01TA")
      (description "NIDEC COPAL ELECTRONICS - CHS-01TA - DIP SWITCH, 1POS, SPST, SLIDE, SMD")
      (fields (field (name "MANUFACTURER") "Nidec Copal"))
      (libsource (lib "eElectroMechanical") (part "CHS-01TA"))
    )
    (comp (ref "SW2")
      (value "CHS-01TA")
      (footprint "CHS-01TA")
      (description "NIDEC COPAL ELECTRONICS - CHS-01TA - DIP SWITCH, 1POS, SPST, SLIDE, SMD")
      (fields (field (name "MANUFACTURER") "Nidec Copal"))
      (libsource (lib "eElectroMechanical") (part "CHS-01TA"))
    )
    (comp (ref "SW3")
      (value "CHS-01TA")
      (footprint "CHS-01TA")
      (description "NIDEC COPAL ELECTRONICS - CHS-01TA - DIP SWITCH, 1POS, SPST, SLIDE, SMD")
      (fields (field (name "MANUFACTURER") "Nidec Copal"))
      (libsource (lib "eElectroMechanical") (part "CHS-01TA"))
    )
    (comp (ref "TP1")
      (value "SMT_TEST")
      (footprint "SMT_TP - 25 x 50")
      (libsource (lib "eTestPoint") (part "SMT_TEST"))
    )
    (comp (ref "TP2")
      (value "SMT_TEST")
      (footprint "SMT_TP - 35")
      (libsource (lib "eTestPoint") (part "SMT_TEST"))
    )
    (comp (ref "TP3")
      (value "SMT_TEST")
      (footprint "SMT_TP - 35")
      (libsource (lib "eTestPoint") (part "SMT_TEST"))
    )
    (comp (ref "TP4")
      (value "SMT_TEST")
      (footprint "SMT_TP - 35")
      (libsource (lib "eTestPoint") (part "SMT_TEST"))
    )
    (comp (ref "TP5")
      (value "SMT_TEST")
      (footprint "SMT_TP - 35")
      (libsource (lib "eTestPoint") (part "SMT_TEST"))
    )
    (comp (ref "TP6")
      (value "SMT_TEST")
      (footprint "SMT_TP - 35")
      (libsource (lib "eTestPoint") (part "SMT_TEST"))
    )
    (comp (ref "TP7")
      (value "SMT_TEST")
      (footprint "SMT_TP - 35")
      (libsource (lib "eTestPoint") (part "SMT_TEST"))
    )
    (comp (ref "U1")
      (value "MIMXRT685SFVKB")
      (footprint "VFBGA176")
      (description "SOC i.MX ARM Cortex M33 176-Pin VFBGA Tray")
      (fields (field (name "MANUFACTURER") "NXP Semiconductors"))
      (libsource (lib "eIC") (part "MIMXRT685SFVKB"))
    )
    (comp (ref "U2")
      (value "PCA9420BSAZ")
      (footprint "PCA9420")
      (description "Power Management IC for Low-Power Microcontroller Applications 24-Pin HVQFN")
      (fields (field (name "MANUFACTURER") "NXP Semiconductors"))
      (libsource (lib "eIC") (part "PCA9420BSAZ"))
    )
    (comp (ref "U3")
      (value "SN74AUC1G07DBVR")
      (footprint "SOT23-5")
      (description "IC BUFF NON-INVERT 2.7 V SOT23-5")
      (fields (field (name "MANUFACTURER") "Texas Instruments"))
      (libsource (lib "eIC") (part "SN74AUC1G07DBVR"))
    )
    (comp (ref "U4")
      (value "PRTR5V0U2X,215")
      (footprint "SOT143B")
      (description "TVS DIODE 5.5VWM SOT143B")
      (fields (field (name "MANUFACTURER") "NXP Semiconductors"))
      (libsource (lib "eDiode") (part "PRTR5V0U2X,215"))
    )
    (comp (ref "U5")
      (value "24MHz")
      (footprint "ABM3")
      (description "CRYSTAL 24.000MHZ 18PF SMD")
      (fields
        (field (name "MANUFACTURER") "Abracon Corporation")
        (field (name "MANUFACTURER PART NUMBER") "ABM3-24.000MHZ-B2-T")
      )
      (libsource (lib "eCrystal") (part "ABM3-24.000MHZ-B2-T"))
    )
    (comp (ref "U6")
      (value "W25Q64JVSIM")
      (footprint "SOIC127P830X200-8L")
      (description "NOR Flash Serial (SPI, Dual SPI, Quad SPI) 3V/3.3V 128M-bit 16M x 8 6ns 8-Pin SOIC Tube")
      (fields
        (field (name "MANUFACTURER") "Winbond")
        (field (name "MANUFACTURER PART NUMBER") "W25Q64JVSSIQ")
      )
      (libsource (lib "eIC") (part "W25Q128JVSIM"))
    )
    (comp (ref "U7")
      (value "ER-TFT1.54-1")
      (footprint "ER-TFT1.54-1")
      (description "1.54\" 240x240 IPS Display")
      (fields (field (name "MANUFACTURER") "Buy Display"))
      (libsource (lib "eDisplay") (part "ER-TFT1.54-1"))
    )
  )
  (nets
    (net (code "1") (name "+1v8") (class "Default")
      (node (ref "C36") (pin "2") (pinfunction "2_2") (pintype "passive"))
      (node (ref "C37") (pin "2") (pinfunction "2_2") (pintype "passive"))
      (node (ref "C38") (pin "2") (pinfunction "2_2") (pintype "passive"))
      (node (ref "C39") (pin "2") (pinfunction "2_2") (pintype "passive"))
      (node (ref "C40") (pin "2") (pinfunction "2_2") (pintype "passive"))
      (node (ref "C41") (pin "2") (pinfunction "2_2") (pintype "passive"))
      (node (ref "C6") (pin "2") (pinfunction "2_2") (pintype "passive"))
      (node (ref "R10") (pin "2") (pinfunction "2_2") (pintype "passive"))
      (node (ref "R3") (pin "2") (pinfunction "2_2") (pintype "passive"))
      (node (ref "R4") (pin "2") (pinfunction "2_2") (pintype "passive"))
      (node (ref "U1") (pin "A13") (pinfunction "VDD1V8_1_A13") (pintype "power_in"))
      (node (ref "U1") (pin "B11") (pinfunction "VDD1V8_B11") (pintype "power_in"))
      (node (ref "U1") (pin "C16") (pinfunction "VDD1V8_C16") (pintype "power_in"))
      (node (ref "U1") (pin "C17") (pinfunction "VDD1V8_C17") (pintype "power_in"))
      (node (ref "U1") (pin "C4") (pinfunction "VDDA_BIAS_C4") (pintype "power_in"))
      (node (ref "U1") (pin "D2") (pinfunction "VREFP_D2") (pintype "power_in"))
      (node (ref "U1") (pin "E15") (pinfunction "VDD1V8_E15") (pintype "power_in"))
      (node (ref "U1") (pin "E4") (pinfunction "VDDA_ADC1V8_E4") (pintype "power_in"))
      (node (ref "U1") (pin "F13") (pinfunction "VDD1V8_F13") (pintype "power_in"))
      (node (ref "U1") (pin "G14") (pinfunction "VDD1V8_G14") (pintype "power_in"))
      (node (ref "U1") (pin "L4") (pinfunction "VDD1V8_L4") (pintype "power_in"))
      (node (ref "U1") (pin "R15") (pinfunction "VDD1V8_R15") (pintype "power_in"))
    )
    (net (code "2") (name "+1v8_AO") (class "Default")
      (node (ref "C10") (pin "2") (pinfunction "1_2") (pintype "passive"))
      (node (ref "R2") (pin "2") (pinfunction "2_2") (pintype "passive"))
      (node (ref "R5") (pin "2") (pinfunction "2_2") (pintype "passive"))
      (node (ref "U1") (pin "C13") (pinfunction "VDD_AO1V8_C13") (pintype "power_in"))
      (node (ref "U1") (pin "D13") (pinfunction "VDD_AO1V8_D13") (pintype "power_in"))
      (node (ref "U2") (pin "12") (pinfunction "LDO1_OUT_12") (pintype "power_in"))
      (node (ref "U3") (pin "5") (pinfunction "VCC_5") (pintype "passive"))
    )
    (net (code "3") (name "+3v3") (class "Default")
      (node (ref "C12") (pin "2") (pinfunction "2_2") (pintype "passive"))
      (node (ref "C13") (pin "2") (pinfunction "2_2") (pintype "passive"))
      (node (ref "C14") (pin "2") (pinfunction "2_2") (pintype "passive"))
      (node (ref "C15") (pin "2") (pinfunction "2_2") (pintype "passive"))
      (node (ref "C16") (pin "2") (pinfunction "2_2") (pintype "passive"))
      (node (ref "C17") (pin "2") (pinfunction "2_2") (pintype "passive"))
      (node (ref "C18") (pin "2") (pinfunction "1_2") (pintype "passive"))
      (node (ref "C20") (pin "2") (pinfunction "2_2") (pintype "passive"))
      (node (ref "C21") (pin "2") (pinfunction "2_2") (pintype "passive"))
      (node (ref "C22") (pin "2") (pinfunction "2_2") (pintype "passive"))
      (node (ref "C23") (pin "2") (pinfunction "2_2") (pintype "passive"))
      (node (ref "C24") (pin "2") (pinfunction "2_2") (pintype "passive"))
      (node (ref "C25") (pin "2") (pinfunction "2_2") (pintype "passive"))
      (node (ref "C42") (pin "2") (pinfunction "1_2") (pintype "passive"))
      (node (ref "C43") (pin "1") (pinfunction "1_1") (pintype "passive"))
      (node (ref "J3") (pin "1") (pinfunction "VCC_1") (pintype "passive"))
      (node (ref "P10") (pin "1") (pinfunction "1_1") (pintype "passive"))
      (node (ref "R12") (pin "2") (pinfunction "2_2") (pintype "passive"))
      (node (ref "R13") (pin "2") (pinfunction "2_2") (pintype "passive"))
      (node (ref "R14") (pin "2") (pinfunction "2_2") (pintype "passive"))
      (node (ref "R8") (pin "2") (pinfunction "2_2") (pintype "passive"))
      (node (ref "U1") (pin "E10") (pinfunction "VDDIO_1_E10") (pintype "power_in"))
      (node (ref "U1") (pin "E6") (pinfunction "VDDIO_1_E6") (pintype "power_in"))
      (node (ref "U1") (pin "E8") (pinfunction "VDDIO_1_E8") (pintype "power_in"))
      (node (ref "U1") (pin "F5") (pinfunction "VDDIO_0_F5") (pintype "power_in"))
      (node (ref "U1") (pin "H13") (pinfunction "VDDIO_1_H13") (pintype "power_in"))
      (node (ref "U1") (pin "H14") (pinfunction "VDDIO_1_H14") (pintype "power_in"))
      (node (ref "U1") (pin "H5") (pinfunction "VDDIO_0_H5") (pintype "power_in"))
      (node (ref "U1") (pin "K13") (pinfunction "VDDIO_1_K13") (pintype "power_in"))
      (node (ref "U1") (pin "K5") (pinfunction "VDDIO_0_K5") (pintype "power_in"))
      (node (ref "U1") (pin "L14") (pinfunction "VDDIO_1_L14") (pintype "power_in"))
      (node (ref "U1") (pin "M5") (pinfunction "VDDIO_0_M5") (pintype "power_in"))
      (node (ref "U1") (pin "N10") (pinfunction "VDDIO_0_N10") (pintype "power_in"))
      (node (ref "U1") (pin "N12") (pinfunction "VDDIO_2_N12") (pintype "power_in"))
      (node (ref "U1") (pin "N16") (pinfunction "USB1_VDD3V3_N16") (pintype "power_in"))
      (node (ref "U1") (pin "N6") (pinfunction "VDDIO_0_N6") (pintype "power_in"))
      (node (ref "U1") (pin "N8") (pinfunction "VDDIO_0_N8") (pintype "power_in"))
      (node (ref "U1") (pin "P11") (pinfunction "VDDIO_2_P11") (pintype "power_in"))
      (node (ref "U1") (pin "P12") (pinfunction "VDDIO_2_P12") (pintype "power_in"))
      (node (ref "U2") (pin "15") (pinfunction "LDO2_OUT_15") (pintype "power_in"))
      (node (ref "U6") (pin "8") (pinfunction "VCC_8") (pintype "passive"))
      (node (ref "U7") (pin "3") (pinfunction "LEDA_3") (pintype "passive"))
      (node (ref "U7") (pin "4") (pinfunction "VDD_4") (pintype "passive"))
    )
    (net (code "4") (name "+5vUSB") (class "Default")
      (node (ref "D2") (pin "1") (pinfunction "A_1") (pintype "passive"))
      (node (ref "L1") (pin "2") (pinfunction "2_2") (pintype "passive"))
      (node (ref "P12") (pin "1") (pinfunction "1_1") (pintype "passive"))
      (node (ref "U1") (pin "R16") (pinfunction "USB1_VBUS_R16") (pintype "input"))
      (node (ref "U4") (pin "4") (pinfunction "VCC_4") (pintype "passive"))
    )
    (net (code "5") (name "+VBATT") (class "Default")
      (node (ref "C4") (pin "2") (pinfunction "1_2") (pintype "passive"))
      (node (ref "J1") (pin "2") (pinfunction "2_2") (pintype "passive"))
      (node (ref "P9") (pin "1") (pinfunction "1_1") (pintype "passive"))
      (node (ref "R6") (pin "2") (pinfunction "2_2") (pintype "passive"))
      (node (ref "U2") (pin "18") (pinfunction "VBAT_18") (pintype "power_in"))
    )
    (net (code "6") (name "+VBATT_BU") (class "Default")
      (node (ref "C3") (pin "2") (pinfunction "1_2") (pintype "passive"))
      (node (ref "R6") (pin "1") (pinfunction "1_1") (pintype "passive"))
      (node (ref "U2") (pin "13") (pinfunction "VBAT_BKUP_13") (pintype "power_in"))
    )
    (net (code "7") (name "+VIN") (class "Default")
      (node (ref "D1") (pin "1") (pinfunction "A_1") (pintype "passive"))
      (node (ref "P11") (pin "1") (pinfunction "1_1") (pintype "passive"))
    )
    (net (code "8") (name "/ADC0_0") (class "Default")
      (node (ref "P43") (pin "1") (pinfunction "1_1") (pintype "passive"))
      (node (ref "U1") (pin "F4") (pinfunction "PIO0_5/FC0_SSEL2/SCT0_GPI0/SCT0_OUT0/CTIMER_INP1/SEC_PIO0_5/ADC0_0_F4") (pintype "passive"))
    )
    (net (code "9") (name "/ADC0_1") (class "Default")
      (node (ref "P45") (pin "1") (pinfunction "1_1") (pintype "passive"))
      (node (ref "U1") (pin "E3") (pinfunction "PIO0_12/FC1_SSEL2/SCT0_GPI2/SCT0_OUT2/CTIMER_INP3/SEC_PIO0_12/ADC0_1_E3") (pintype "passive"))
    )
    (net (code "10") (name "/ADC0_8") (class "Default")
      (node (ref "P44") (pin "1") (pinfunction "1_1") (pintype "passive"))
      (node (ref "U1") (pin "E1") (pinfunction "PIO0_6/FC0_SSEL3/SCT0_GPI1/SCT0_OUT1/CTIMER0_MAT0/SEC_PIO0_6/ADC0_8_E1") (pintype "passive"))
    )
    (net (code "11") (name "/BTN") (class "Default")
      (node (ref "BTN1") (pin "2") (pinfunction "2_2") (pintype "passive"))
      (node (ref "U1") (pin "U17") (pinfunction "PIO2_8/SD0_D7/SCT0_OUT4/CTIMER1_MAT2_U17") (pintype "passive"))
    )
    (net (code "12") (name "/DEBUG_RX_IN") (class "Default")
      (node (ref "P42") (pin "1") (pinfunction "1_1") (pintype "passive"))
      (node (ref "U1") (pin "G4") (pinfunction "PIO0_2/FC0_RXD_SDA_MOSI_DATA/CTIMER0_MAT2/I2S_BRIDGE_DATA_IN/SEC_PIO0_2_G4") (pintype "passive"))
    )
    (net (code "13") (name "/DEBUG_TX_OUT") (class "Default")
      (node (ref "P41") (pin "1") (pinfunction "1_1") (pintype "passive"))
      (node (ref "U1") (pin "G2") (pinfunction "PIO0_1/FC0_TXD_SCL_MISO_WS/CTIMER0_MAT1/I2S_BRIDGE_WS_IN/SEC_PIO0_1_G2") (pintype "passive"))
    )
    (net (code "14") (name "/DM_MCU") (class "Default")
      (node (ref "R9") (pin "2") (pinfunction "2_2") (pintype "passive"))
      (node (ref "U1") (pin "T17") (pinfunction "USB1_DM_T17") (pintype "bidirectional"))
    )
    (net (code "15") (name "/DP_MCU") (class "Default")
      (node (ref "R11") (pin "2") (pinfunction "2_2") (pintype "passive"))
      (node (ref "U1") (pin "R17") (pinfunction "USB1_DP_R17") (pintype "bidirectional"))
    )
    (net (code "16") (name "/FC2_CLK") (class "Default")
      (node (ref "P48") (pin "1") (pinfunction "1_1") (pintype "passive"))
      (node (ref "U1") (pin "A3") (pinfunction "PIO0_14/FC2_SCK/SCT0_GPI0/SCT0_OUT0/CTIMER2_MAT0/I2S_BRIDGE_CLK_IN/SEC_PIO0_14_A3") (pintype "passive"))
    )
    (net (code "17") (name "/FC2_SDA") (class "Default")
      (node (ref "P46") (pin "1") (pinfunction "1_1") (pintype "passive"))
      (node (ref "U1") (pin "D6") (pinfunction "PIO0_16/FC2_RXD_SDA_MOSI_DATA/SCT0_GPI2/SCT0_OUT2/CTIMER2_MAT2/I2S_BRIDGE_DATA_IN/SEC_PIO0_16_D6") (pintype "passive"))
    )
    (net (code "18") (name "/FC2_WS") (class "Default")
      (node (ref "P47") (pin "1") (pinfunction "1_1") (pintype "passive"))
      (node (ref "U1") (pin "A5") (pinfunction "PIO0_15/FC2_TXD_SCL_MISO_WS/SCT0_GPI1/SCT0_OUT1/CTIMER2_MAT1/I2S_BRIDGE_WS_IN/SEC_PIO0_15_A5") (pintype "passive"))
    )
    (net (code "19") (name "/FC3_CLK") (class "Default")
      (node (ref "P1") (pin "1") (pinfunction "1_1") (pintype "passive"))
      (node (ref "U1") (pin "C7") (pinfunction "PIO0_21/FC3_SCK/CTIMER3_MAT0/TRACECLK/SEC_PIO0_21_C7") (pintype "passive"))
    )
    (net (code "20") (name "/FC3_SDA") (class "Default")
      (node (ref "P3") (pin "1") (pinfunction "1_1") (pintype "passive"))
      (node (ref "U1") (pin "C9") (pinfunction "PIO0_23/FC3_RXD_SDA_MOSI_DATA/CTIMER3_MAT2/TRACEDATA(1)/SEC_PIO0_23_C9") (pintype "passive"))
    )
    (net (code "21") (name "/FC3_WS") (class "Default")
      (node (ref "P2") (pin "1") (pinfunction "1_1") (pintype "passive"))
      (node (ref "U1") (pin "D8") (pinfunction "PIO0_22/FC3_TXD_SCL_MISO_WS/CTIMER3_MAT1/TRACEDATA(0)/SEC_PIO0_22_D8") (pintype "passive"))
    )
    (net (code "22") (name "/FC4_CLK") (class "Default")
      (node (ref "U1") (pin "D11") (pinfunction "PIO0_28/FC4_SCK/CTIMER4_MAT0/I2S_BRIDGE_CLK_OUT/SEC_PIO0_28_D11") (pintype "passive"))
    )
    (net (code "23") (name "/FC4_SDA") (class "Default")
      (node (ref "U1") (pin "C11") (pinfunction "PIO0_30/FC4_RXD_SDA_MOSI_DATA/CTIMER4_MAT2/I2S_BRIDGE_DATA_OUT/SEC_PIO0_30_C11") (pintype "passive"))
    )
    (net (code "24") (name "/FC4_WS") (class "Default")
      (node (ref "U1") (pin "B10") (pinfunction "PIO0_29/FC4_TXD_SCL_MISO_WS/CTIMER4_MAT1/I2S_BRIDGE_WS_OUT/SEC_PIO0_29_B10") (pintype "passive"))
    )
    (net (code "25") (name "/FC5_RXD") (class "Default")
      (node (ref "P6") (pin "1") (pinfunction "1_1") (pintype "passive"))
      (node (ref "U1") (pin "J16") (pinfunction "PIO1_5/FC5_RXD_SDA_MOSI_DATA_J16") (pintype "passive"))
    )
    (net (code "26") (name "/FC5_SCK") (class "Default")
      (node (ref "P4") (pin "1") (pinfunction "1_1") (pintype "passive"))
      (node (ref "U1") (pin "G16") (pinfunction "PIO1_3/FC5_SCK_G16") (pintype "passive"))
    )
    (net (code "27") (name "/FC5_SSEL0") (class "Default")
      (node (ref "P7") (pin "1") (pinfunction "1_1") (pintype "passive"))
      (node (ref "U1") (pin "J17") (pinfunction "PIO1_6/FC5_CTS_SDA_SSEL0/SCT0_GPI4/SCT0_OUT4/FC4_SSEL2_J17") (pintype "passive"))
    )
    (net (code "28") (name "/FC5_TXD") (class "Default")
      (node (ref "P5") (pin "1") (pinfunction "1_1") (pintype "passive"))
      (node (ref "U1") (pin "G17") (pinfunction "PIO1_4/FC5_TXD_SCL_MISO_WS_G17") (pintype "passive"))
    )
    (net (code "29") (name "/HS_SPI_MISO") (class "Default")
      (node (ref "U1") (pin "M2") (pinfunction "PIO1_12/HS_SPI_MISO/CTIMER2_MAT1/FLEXSPI0B_DATA1_M2") (pintype "passive"))
    )
    (net (code "30") (name "/HS_SPI_MOSI") (class "Default")
      (node (ref "U1") (pin "N1") (pinfunction "PIO1_13/HS_SPI_MOSI/CTIMER2_MAT2/FLEXSPI0B_DATA2_N1") (pintype "passive"))
      (node (ref "U7") (pin "10") (pinfunction "SDA_10") (pintype "passive"))
    )
    (net (code "31") (name "/HS_SPI_SCK") (class "Default")
      (node (ref "U1") (pin "L2") (pinfunction "PIO1_11/HS_SPI_SCK/CTIMER2_MAT0/FLEXSPI0B_DATA0_L2") (pintype "passive"))
      (node (ref "U7") (pin "9") (pinfunction "SCL_9") (pintype "passive"))
    )
    (net (code "32") (name "/HS_SPI_SSEL0") (class "Default")
      (node (ref "U1") (pin "N2") (pinfunction "PIO1_14/HS_SPI_SSEL0/CTIMER2_MAT3/FLEXSPI0B_DATA3_N2") (pintype "passive"))
      (node (ref "U7") (pin "8") (pinfunction "CS_8") (pintype "passive"))
    )
    (net (code "33") (name "/I3C0_PUR") (class "Default")
      (node (ref "R16") (pin "1") (pinfunction "1_1") (pintype "passive"))
      (node (ref "U1") (pin "B6") (pinfunction "PIO2_31/I3C0_PUR/SCT0_OUT7/UTICK_CAP3/CTIMER_INP15/SWO/CMP0_B_B6") (pintype "passive"))
    )
    (net (code "34") (name "/I3C0_SCL") (class "Default")
      (node (ref "P15") (pin "1") (pinfunction "1_1") (pintype "passive"))
      (node (ref "U1") (pin "N17") (pinfunction "PIO2_29/I3C0_SCL/SCT0_OUT0/CLKOUT_N17") (pintype "passive"))
    )
    (net (code "35") (name "/I3C0_SDA") (class "Default")
      (node (ref "P16") (pin "1") (pinfunction "1_1") (pintype "passive"))
      (node (ref "R16") (pin "2") (pinfunction "2_2") (pintype "passive"))
      (node (ref "U1") (pin "P16") (pinfunction "PIO2_30/I3C0_SDA/SCT0_OUT3/CLKIN/CMP0_OUT_P16") (pintype "passive"))
    )
    (net (code "36") (name "/ISP0") (class "Default")
      (node (ref "R12") (pin "1") (pinfunction "1_1") (pintype "passive"))
      (node (ref "SW1") (pin "2") (pinfunction "2_2") (pintype "passive"))
      (node (ref "U1") (pin "N3") (pinfunction "PIO1_15/HS_SPI_SSEL1/CTIMER3_MAT0/ISP0_N3") (pintype "passive"))
    )
    (net (code "37") (name "/ISP1") (class "Default")
      (node (ref "R13") (pin "1") (pinfunction "1_1") (pintype "passive"))
      (node (ref "SW2") (pin "2") (pinfunction "2_2") (pintype "passive"))
      (node (ref "U1") (pin "M4") (pinfunction "PIO1_16/HS_SPI_SSEL2/SCT0_OUT8/CTIMER3_MAT1/ISP1_M4") (pintype "passive"))
    )
    (net (code "38") (name "/ISP2") (class "Default")
      (node (ref "R14") (pin "1") (pinfunction "1_1") (pintype "passive"))
      (node (ref "SW3") (pin "2") (pinfunction "2_2") (pintype "passive"))
      (node (ref "U1") (pin "N4") (pinfunction "PIO1_17/HS_SPI_SSEL3/SCT0_OUT9/CTIMER3_MAT2/ISP2_N4") (pintype "passive"))
    )
    (net (code "39") (name "/LCD_BL") (class "Default")
      (node (ref "Q1") (pin "1") (pinfunction "G_1") (pintype "passive"))
      (node (ref "U1") (pin "U16") (pinfunction "PIO2_7/SD0_D6/SCT0_GPI5/CTIMER1_MAT1_U16") (pintype "passive"))
    )
    (net (code "40") (name "/LCD_CMD_DATA") (class "Default")
      (node (ref "U1") (pin "U13") (pinfunction "PIO2_5/SD0_D4/SCT0_OUT3_U13") (pintype "passive"))
      (node (ref "U7") (pin "7") (pinfunction "D/C_7") (pintype "passive"))
    )
    (net (code "41") (name "/LCD_RST") (class "Default")
      (node (ref "U1") (pin "U15") (pinfunction "PIO2_6/SD0_D5/SCT0_GPI4/CTIMER1_MAT0_U15") (pintype "passive"))
      (node (ref "U7") (pin "11") (pinfunction "RESET_11") (pintype "passive"))
    )
    (net (code "42") (name "/MCLK") (class "Default")
      (node (ref "P14") (pin "1") (pinfunction "1_1") (pintype "passive"))
      (node (ref "U1") (pin "K16") (pinfunction "PIO1_10/MCLK/FREQME_GPIO_CLK/CTIMER_INP10/CLKOUT_K16") (pintype "passive"))
    )
    (net (code "43") (name "/PDM_CLK01") (class "Default")
      (node (ref "P38") (pin "1") (pinfunction "1_1") (pintype "passive"))
      (node (ref "U1") (pin "R1") (pinfunction "PIO2_16/PDM_CLK01_R1") (pintype "passive"))
    )
    (net (code "44") (name "/PDM_CLK23") (class "Default")
      (node (ref "P36") (pin "1") (pinfunction "1_1") (pintype "passive"))
      (node (ref "U1") (pin "U1") (pinfunction "PIO2_17/PDM_CLK23/FLEXSPI0B_DATA4_U1") (pintype "passive"))
    )
    (net (code "45") (name "/PDM_CLK45") (class "Default")
      (node (ref "P34") (pin "1") (pinfunction "1_1") (pintype "passive"))
      (node (ref "U1") (pin "R2") (pinfunction "PIO2_18/PDM_CLK45/FLEXSPI0B_DATA5_R2") (pintype "passive"))
    )
    (net (code "46") (name "/PDM_CLK67") (class "Default")
      (node (ref "P32") (pin "1") (pinfunction "1_1") (pintype "passive"))
      (node (ref "U1") (pin "T2") (pinfunction "PIO2_19/PDM_CLK67/FLEXSPI0B_SS0_N_T2") (pintype "passive"))
    )
    (net (code "47") (name "/PDM_DATA01") (class "Default")
      (node (ref "P37") (pin "1") (pinfunction "1_1") (pintype "passive"))
      (node (ref "U1") (pin "U2") (pinfunction "PIO2_20/PDM_DATA01_U2") (pintype "passive"))
    )
    (net (code "48") (name "/PDM_DATA23") (class "Default")
      (node (ref "P35") (pin "1") (pinfunction "1_1") (pintype "passive"))
      (node (ref "U1") (pin "R3") (pinfunction "PIO2_21/PDM_DATA23/CTIMER_INP14/FLEXSPI0B_SS1_N_R3") (pintype "passive"))
    )
    (net (code "49") (name "/PDM_DATA45") (class "Default")
      (node (ref "P33") (pin "1") (pinfunction "1_1") (pintype "passive"))
      (node (ref "U1") (pin "P3") (pinfunction "PIO2_22/PDM_DATA45/FLEXSPI0B_DATA6_P3") (pintype "passive"))
    )
    (net (code "50") (name "/PDM_DATA67") (class "Default")
      (node (ref "P31") (pin "1") (pinfunction "1_1") (pintype "passive"))
      (node (ref "U1") (pin "P5") (pinfunction "PIO2_23/PDM_DATA67/FLEXSPI0B_DATA7_P5") (pintype "passive"))
    )
    (net (code "51") (name "/PIO0_11") (class "Default")
      (node (ref "P39") (pin "1") (pinfunction "1_1") (pintype "passive"))
      (node (ref "U1") (pin "L1") (pinfunction "PIO0_11/FC1_RTS_SCL_SSEL1/SCT0_GPI0/SCT0_OUT8/CTIMER_INP2/FC0_SSEL3/SEC_PIO0_11_L1") (pintype "passive"))
    )
    (net (code "52") (name "/PIO1_8") (class "Default")
      (node (ref "TP6") (pin "1") (pinfunction "1_1") (pintype "passive"))
      (node (ref "U1") (pin "B5") (pinfunction "PIO1_8/FC5_SSEL2/SCT0_GPI6/CTIMER_INP12/CTIMER1_MAT2/ADC0_4_B5") (pintype "passive"))
    )
    (net (code "53") (name "/PIO1_9") (class "Default")
      (node (ref "TP7") (pin "1") (pinfunction "1_1") (pintype "passive"))
      (node (ref "U1") (pin "B1") (pinfunction "PIO1_9/FC5_SSEL3/SCT0_GPI7/UTICK_CAP1/CTIMER1_MAT3/ADC0_12_B1") (pintype "passive"))
    )
    (net (code "54") (name "/PMIC_INTB") (class "Default")
      (node (ref "R2") (pin "1") (pinfunction "1_1") (pintype "passive"))
      (node (ref "U1") (pin "A15") (pinfunction "~{PMIC_IRQ_N}_A15") (pintype "input"))
      (node (ref "U2") (pin "10") (pinfunction "INTB_10") (pintype "output"))
    )
    (net (code "55") (name "/PMIC_MODE0") (class "Default")
      (node (ref "U1") (pin "C15") (pinfunction "PMIC_MODE0_C15") (pintype "output"))
      (node (ref "U2") (pin "7") (pinfunction "MODESEL0_7") (pintype "input"))
    )
    (net (code "56") (name "/PMIC_MODE1") (class "Default")
      (node (ref "U1") (pin "B16") (pinfunction "PMIC_MODE1_B16") (pintype "output"))
      (node (ref "U2") (pin "8") (pinfunction "MODESEL1_8") (pintype "input"))
    )
    (net (code "57") (name "/PMIC_ON") (class "Default")
      (node (ref "P13") (pin "1") (pinfunction "1_1") (pintype "passive"))
      (node (ref "U2") (pin "4") (pinfunction "ON_4") (pintype "input"))
    )
    (net (code "58") (name "/PMIC_RESETN") (class "Default")
      (node (ref "R5") (pin "1") (pinfunction "1_1") (pintype "passive"))
      (node (ref "U1") (pin "B15") (pinfunction "~{RESETN}_B15") (pintype "input"))
      (node (ref "U2") (pin "11") (pinfunction "SYSRSTN_11") (pintype "output"))
      (node (ref "U3") (pin "4") (pinfunction "Y_4") (pintype "passive"))
    )
    (net (code "59") (name "/PMIC_SCL") (class "Default")
      (node (ref "R3") (pin "1") (pinfunction "1_1") (pintype "passive"))
      (node (ref "U1") (pin "E16") (pinfunction "PMIC_I2C_SCL_E16") (pintype "output"))
      (node (ref "U2") (pin "5") (pinfunction "SCL_5") (pintype "input"))
    )
    (net (code "60") (name "/PMIC_SDA") (class "Default")
      (node (ref "R4") (pin "1") (pinfunction "1_1") (pintype "passive"))
      (node (ref "U1") (pin "F16") (pinfunction "PMIC_I2C_SDA_F16") (pintype "bidirectional"))
      (node (ref "U2") (pin "6") (pinfunction "SDA_6") (pintype "bidirectional"))
    )
    (net (code "61") (name "/QSPI_CS") (class "Default")
      (node (ref "U1") (pin "T4") (pinfunction "PIO1_19/FLEXSPI0A_SS0_N/SCT0_OUT0/CTIMER4_MAT0_T4") (pintype "passive"))
      (node (ref "U6") (pin "1") (pinfunction "~{CE}_1") (pintype "passive"))
    )
    (net (code "62") (name "/QSPI_D0") (class "Default")
      (node (ref "U1") (pin "T5") (pinfunction "PIO1_20/FLEXSPI0A_DATA0/SCT0_GPI1/CTIMER4_MAT1_T5") (pintype "passive"))
      (node (ref "U6") (pin "5") (pinfunction "SI_(IO0)_5") (pintype "passive"))
    )
    (net (code "63") (name "/QSPI_D1") (class "Default")
      (node (ref "U1") (pin "U5") (pinfunction "PIO1_21/FLEXSPI0A_DATA1/SCT0_OUT1/CTIMER4_MAT2_U5") (pintype "passive"))
      (node (ref "U6") (pin "2") (pinfunction "SO_(IO1)_2") (pintype "passive"))
    )
    (net (code "64") (name "/QSPI_D2") (class "Default")
      (node (ref "U1") (pin "P6") (pinfunction "PIO1_22/FLEXSPI0A_DATA2/SCT0_GPI2/CTIMER4_MAT3_P6") (pintype "passive"))
      (node (ref "U6") (pin "3") (pinfunction "~{WP}_(IO2)_3") (pintype "passive"))
    )
    (net (code "65") (name "/QSPI_D3") (class "Default")
      (node (ref "U1") (pin "P7") (pinfunction "PIO1_23/FLEXSPI0A_DATA3/SCT0_OUT2/CTIMER_INP8_P7") (pintype "passive"))
      (node (ref "U6") (pin "7") (pinfunction "~{HOLD}_(IO3)_7") (pintype "passive"))
    )
    (net (code "66") (name "/QSPI_SCK") (class "Default")
      (node (ref "U1") (pin "T9") (pinfunction "PIO1_18/FLEXSPI0A_SCLK/SCT0_GPI0/CTIMER3_MAT3_T9") (pintype "passive"))
      (node (ref "U6") (pin "6") (pinfunction "SCK_6") (pintype "passive"))
    )
    (net (code "67") (name "/RST_3V3") (class "Default")
      (node (ref "J3") (pin "10") (pinfunction "~{RST}_10") (pintype "passive"))
      (node (ref "P20") (pin "1") (pinfunction "1_1") (pintype "passive"))
      (node (ref "R8") (pin "1") (pinfunction "1_1") (pintype "passive"))
      (node (ref "RESET1") (pin "2") (pinfunction "2_2") (pintype "passive"))
      (node (ref "U3") (pin "2") (pinfunction "A_2") (pintype "passive"))
    )
    (net (code "68") (name "/SD_CLK") (class "Default")
      (node (ref "P25") (pin "1") (pinfunction "1_1") (pintype "passive"))
      (node (ref "U1") (pin "P10") (pinfunction "PIO1_30/SD0_CLK/SCT0_GPI0_P10") (pintype "passive"))
    )
    (net (code "69") (name "/SD_CMD") (class "Default")
      (node (ref "P30") (pin "1") (pinfunction "1_1") (pintype "passive"))
      (node (ref "U1") (pin "R9") (pinfunction "PIO1_31/SD0_CMD/SCT0_GPI1_R9") (pintype "passive"))
    )
    (net (code "70") (name "/SD_D0") (class "Default")
      (node (ref "P29") (pin "1") (pinfunction "1_1") (pintype "passive"))
      (node (ref "U1") (pin "R11") (pinfunction "PIO2_0/SD0_D0/SCT0_GPI2_R11") (pintype "passive"))
    )
    (net (code "71") (name "/SD_D1") (class "Default")
      (node (ref "P28") (pin "1") (pinfunction "1_1") (pintype "passive"))
      (node (ref "U1") (pin "T11") (pinfunction "PIO2_1/SD0_D1/SCT0_GPI3_T11") (pintype "passive"))
    )
    (net (code "72") (name "/SD_D2") (class "Default")
      (node (ref "P27") (pin "1") (pinfunction "1_1") (pintype "passive"))
      (node (ref "U1") (pin "U11") (pinfunction "PIO2_2/SD0_D2/SCT0_OUT0_U11") (pintype "passive"))
    )
    (net (code "73") (name "/SD_D3") (class "Default")
      (node (ref "P26") (pin "1") (pinfunction "1_1") (pintype "passive"))
      (node (ref "U1") (pin "T12") (pinfunction "PIO2_3/SD0_D3/SCT0_OUT1_T12") (pintype "passive"))
    )
    (net (code "74") (name "/SD_DETECT_N") (class "Default")
      (node (ref "P24") (pin "1") (pinfunction "1_1") (pintype "passive"))
      (node (ref "U1") (pin "R13") (pinfunction "PIO2_9/SD0_CARD_DET_N/SCT0_OUT5/CTIMER1_MAT3_R13") (pintype "passive"))
    )
    (net (code "75") (name "/SD_RESET_N") (class "Default")
      (node (ref "P23") (pin "1") (pinfunction "1_1") (pintype "passive"))
      (node (ref "U1") (pin "T15") (pinfunction "PIO2_10/SD0_RESET_N/SCT0_GPI6/CTIMER2_MAT0_T15") (pintype "passive"))
    )
    (net (code "76") (name "/SWCLK") (class "Default")
      (node (ref "J3") (pin "4") (pinfunction "SWDCLK/TCK_4") (pintype "passive"))
      (node (ref "P22") (pin "1") (pinfunction "1_1") (pintype "passive"))
      (node (ref "U1") (pin "L17") (pinfunction "PIO2_25/SWCLK_L17") (pintype "passive"))
    )
    (net (code "77") (name "/SWIO") (class "Default")
      (node (ref "J3") (pin "2") (pinfunction "SWDIO/TMS_2") (pintype "passive"))
      (node (ref "P21") (pin "1") (pinfunction "1_1") (pintype "passive"))
      (node (ref "U1") (pin "L15") (pinfunction "PIO2_26/SWDIO_L15") (pintype "passive"))
    )
    (net (code "78") (name "/SWO") (class "Default")
      (node (ref "J3") (pin "6") (pinfunction "SWO/TDO_6") (pintype "passive"))
      (node (ref "U1") (pin "L16") (pinfunction "PIO2_24/SWO/GPIO_INT_BMAT_L16") (pintype "passive"))
    )
    (net (code "79") (name "/TEMP_SENSE") (class "Default")
      (node (ref "TP1") (pin "1") (pinfunction "1_1") (pintype "passive"))
      (node (ref "U2") (pin "14") (pinfunction "TS_14") (pintype "input"))
    )
    (net (code "80") (name "GND") (class "Default")
      (node (ref "BTN1") (pin "1") (pinfunction "1_1") (pintype "passive"))
      (node (ref "BTN1") (pin "S") (pinfunction "SHIELD_S") (pintype "passive"))
      (node (ref "C1") (pin "1") (pinfunction "1_1") (pintype "passive"))
      (node (ref "C10") (pin "1") (pinfunction "1_1") (pintype "passive"))
      (node (ref "C11") (pin "1") (pinfunction "1_1") (pintype "passive"))
      (node (ref "C12") (pin "1") (pinfunction "1_1") (pintype "passive"))
      (node (ref "C13") (pin "1") (pinfunction "1_1") (pintype "passive"))
      (node (ref "C14") (pin "1") (pinfunction "1_1") (pintype "passive"))
      (node (ref "C15") (pin "1") (pinfunction "1_1") (pintype "passive"))
      (node (ref "C16") (pin "1") (pinfunction "1_1") (pintype "passive"))
      (node (ref "C17") (pin "1") (pinfunction "1_1") (pintype "passive"))
      (node (ref "C18") (pin "1") (pinfunction "1_1") (pintype "passive"))
      (node (ref "C19") (pin "1") (pinfunction "1_1") (pintype "passive"))
      (node (ref "C2") (pin "2") (pinfunction "1_2") (pintype "passive"))
      (node (ref "C20") (pin "1") (pinfunction "1_1") (pintype "passive"))
      (node (ref "C21") (pin "1") (pinfunction "1_1") (pintype "passive"))
      (node (ref "C22") (pin "1") (pinfunction "1_1") (pintype "passive"))
      (node (ref "C23") (pin "1") (pinfunction "1_1") (pintype "passive"))
      (node (ref "C24") (pin "1") (pinfunction "1_1") (pintype "passive"))
      (node (ref "C25") (pin "1") (pinfunction "1_1") (pintype "passive"))
      (node (ref "C26") (pin "1") (pinfunction "1_1") (pintype "passive"))
      (node (ref "C27") (pin "1") (pinfunction "1_1") (pintype "passive"))
      (node (ref "C28") (pin "1") (pinfunction "1_1") (pintype "passive"))
      (node (ref "C29") (pin "1") (pinfunction "1_1") (pintype "passive"))
      (node (ref "C3") (pin "1") (pinfunction "1_1") (pintype "passive"))
      (node (ref "C30") (pin "1") (pinfunction "1_1") (pintype "passive"))
      (node (ref "C31") (pin "1") (pinfunction "1_1") (pintype "passive"))
      (node (ref "C32") (pin "1") (pinfunction "1_1") (pintype "passive"))
      (node (ref "C33") (pin "1") (pinfunction "1_1") (pintype "passive"))
      (node (ref "C34") (pin "1") (pinfunction "1_1") (pintype "passive"))
      (node (ref "C35") (pin "1") (pinfunction "1_1") (pintype "passive"))
      (node (ref "C36") (pin "1") (pinfunction "1_1") (pintype "passive"))
      (node (ref "C37") (pin "1") (pinfunction "1_1") (pintype "passive"))
      (node (ref "C38") (pin "1") (pinfunction "1_1") (pintype "passive"))
      (node (ref "C39") (pin "1") (pinfunction "1_1") (pintype "passive"))
      (node (ref "C4") (pin "1") (pinfunction "1_1") (pintype "passive"))
      (node (ref "C40") (pin "1") (pinfunction "1_1") (pintype "passive"))
      (node (ref "C41") (pin "1") (pinfunction "1_1") (pintype "passive"))
      (node (ref "C42") (pin "1") (pinfunction "1_1") (pintype "passive"))
      (node (ref "C43") (pin "2") (pinfunction "1_2") (pintype "passive"))
      (node (ref "C5") (pin "2") (pinfunction "1_2") (pintype "passive"))
      (node (ref "C6") (pin "1") (pinfunction "1_1") (pintype "passive"))
      (node (ref "C7") (pin "1") (pinfunction "1_1") (pintype "passive"))
      (node (ref "C8") (pin "2") (pinfunction "1_2") (pintype "passive"))
      (node (ref "C9") (pin "1") (pinfunction "1_1") (pintype "passive"))
      (node (ref "J1") (pin "1") (pinfunction "1_1") (pintype "passive"))
      (node (ref "J2") (pin "4") (pinfunction "ID_4") (pintype "passive"))
      (node (ref "J2") (pin "5") (pinfunction "GND_5") (pintype "passive"))
      (node (ref "J2") (pin "MOUNT") (pinfunction "MOUNT_MOUNT") (pintype "passive"))
      (node (ref "J3") (pin "3") (pinfunction "GND_3") (pintype "passive"))
      (node (ref "J3") (pin "5") (pinfunction "GND_5") (pintype "passive"))
      (node (ref "J3") (pin "9") (pinfunction "GND_DETECT_9") (pintype "passive"))
      (node (ref "P40") (pin "1") (pinfunction "1_1") (pintype "passive"))
      (node (ref "P8") (pin "1") (pinfunction "1_1") (pintype "passive"))
      (node (ref "Q1") (pin "2") (pinfunction "2_2") (pintype "passive"))
      (node (ref "R1") (pin "1") (pinfunction "1_1") (pintype "passive"))
      (node (ref "RESET1") (pin "1") (pinfunction "1_1") (pintype "passive"))
      (node (ref "RESET1") (pin "S") (pinfunction "SHIELD_S") (pintype "passive"))
      (node (ref "SW1") (pin "1") (pinfunction "1_1") (pintype "passive"))
      (node (ref "SW2") (pin "1") (pinfunction "1_1") (pintype "passive"))
      (node (ref "SW3") (pin "1") (pinfunction "1_1") (pintype "passive"))
      (node (ref "U1") (pin "C2") (pinfunction "VREFN_C2") (pintype "power_in"))
      (node (ref "U1") (pin "C3") (pinfunction "VSSA_C3") (pintype "power_in"))
      (node (ref "U1") (pin "D12") (pinfunction "VSSA_D12") (pintype "power_in"))
      (node (ref "U1") (pin "D15") (pinfunction "VSS_D15") (pintype "power_in"))
      (node (ref "U1") (pin "D5") (pinfunction "VSS_D5") (pintype "power_in"))
      (node (ref "U1") (pin "E12") (pinfunction "VSS_E12") (pintype "power_in"))
      (node (ref "U1") (pin "E14") (pinfunction "VSS_E14") (pintype "power_in"))
      (node (ref "U1") (pin "F11") (pinfunction "VSS_F11") (pintype "power_in"))
      (node (ref "U1") (pin "F7") (pinfunction "VSS_F7") (pintype "power_in"))
      (node (ref "U1") (pin "G12") (pinfunction "VSS_G12") (pintype "power_in"))
      (node (ref "U1") (pin "G6") (pinfunction "VSS_G6") (pintype "power_in"))
      (node (ref "U1") (pin "H10") (pinfunction "VSS_H10") (pintype "power_in"))
      (node (ref "U1") (pin "H8") (pinfunction "VSS_H8") (pintype "power_in"))
      (node (ref "U1") (pin "H9") (pinfunction "VSS_H9") (pintype "power_in"))
      (node (ref "U1") (pin "J10") (pinfunction "VSS_J10") (pintype "power_in"))
      (node (ref "U1") (pin "J8") (pinfunction "VSS_J8") (pintype "power_in"))
      (node (ref "U1") (pin "K10") (pinfunction "VSS_K10") (pintype "power_in"))
      (node (ref "U1") (pin "K8") (pinfunction "VSS_K8") (pintype "power_in"))
      (node (ref "U1") (pin "K9") (pinfunction "VSS_K9") (pintype "power_in"))
      (node (ref "U1") (pin "L12") (pinfunction "VSS_L12") (pintype "power_in"))
      (node (ref "U1") (pin "L6") (pinfunction "VSS_L6") (pintype "power_in"))
      (node (ref "U1") (pin "M11") (pinfunction "VSS_M11") (pintype "power_in"))
      (node (ref "U1") (pin "M13") (pinfunction "VSS_M13") (pintype "power_in"))
      (node (ref "U1") (pin "M7") (pinfunction "VSS_M7") (pintype "power_in"))
      (node (ref "U1") (pin "N14") (pinfunction "VSS_N14") (pintype "power_in"))
      (node (ref "U1") (pin "P13") (pinfunction "VSS_P13") (pintype "power_in"))
      (node (ref "U2") (pin "21") (pinfunction "AGND2_21") (pintype "power_in"))
      (node (ref "U2") (pin "23") (pinfunction "PGND1_23") (pintype "power_in"))
      (node (ref "U2") (pin "24") (pinfunction "PGND2_24") (pintype "power_in"))
      (node (ref "U2") (pin "25") (pinfunction "EXP_25") (pintype "power_in"))
      (node (ref "U2") (pin "9") (pinfunction "AGND1_9") (pintype "power_in"))
      (node (ref "U3") (pin "3") (pinfunction "GND_3") (pintype "passive"))
      (node (ref "U4") (pin "1") (pinfunction "GND_1") (pintype "passive"))
      (node (ref "U6") (pin "4") (pinfunction "GND_4") (pintype "passive"))
      (node (ref "U7") (pin "1") (pinfunction "GND_1") (pintype "passive"))
      (node (ref "U7") (pin "12") (pinfunction "GND_12") (pintype "passive"))
      (node (ref "U7") (pin "5") (pinfunction "GND_5") (pintype "passive"))
      (node (ref "U7") (pin "6") (pinfunction "GND_6") (pintype "passive"))
    )
    (net (code "81") (name "Net-(D1-K)") (class "Default")
      (node (ref "C1") (pin "2") (pinfunction "1_2") (pintype "passive"))
      (node (ref "D1") (pin "2") (pinfunction "K_2") (pintype "passive"))
      (node (ref "D2") (pin "2") (pinfunction "K_2") (pintype "passive"))
      (node (ref "U2") (pin "16") (pinfunction "VIN_16") (pintype "power_in"))
    )
    (net (code "82") (name "Net-(J2-+5v)") (class "Default")
      (node (ref "J2") (pin "1") (pinfunction "+5v_1") (pintype "passive"))
      (node (ref "L1") (pin "1") (pinfunction "1_1") (pintype "passive"))
    )
    (net (code "83") (name "Net-(J2-D+)") (class "Default")
      (node (ref "J2") (pin "3") (pinfunction "D+_3") (pintype "passive"))
      (node (ref "R11") (pin "1") (pinfunction "1_1") (pintype "passive"))
      (node (ref "U4") (pin "3") (pinfunction "IO2_3") (pintype "passive"))
    )
    (net (code "84") (name "Net-(J2-D-)") (class "Default")
      (node (ref "J2") (pin "2") (pinfunction "D-_2") (pintype "passive"))
      (node (ref "R9") (pin "1") (pinfunction "1_1") (pintype "passive"))
      (node (ref "U4") (pin "2") (pinfunction "IO1_2") (pintype "passive"))
    )
    (net (code "85") (name "Net-(Q1-D)") (class "Default")
      (node (ref "Q1") (pin "3") (pinfunction "D_3") (pintype "passive"))
      (node (ref "R15") (pin "1") (pinfunction "1_1") (pintype "passive"))
    )
    (net (code "86") (name "Net-(U1C-LDO_ENABLE)") (class "Default")
      (node (ref "R1") (pin "2") (pinfunction "2_2") (pintype "passive"))
      (node (ref "U1") (pin "A16") (pinfunction "LDO_ENABLE_A16") (pintype "input"))
    )
    (net (code "87") (name "Net-(U1D-PIO0_4{slash}FC0_RTS_SCL_SSEL1{slash}CTIMER_INP0{slash}FC1_SSEL3{slash}CMP0_OUT{slash}SEC_PIO0_4)") (class "Default")
      (node (ref "TP2") (pin "1") (pinfunction "1_1") (pintype "passive"))
      (node (ref "U1") (pin "J1") (pinfunction "PIO0_4/FC0_RTS_SCL_SSEL1/CTIMER_INP0/FC1_SSEL3/CMP0_OUT/SEC_PIO0_4_J1") (pintype "passive"))
    )
    (net (code "88") (name "Net-(U1D-PIO2_14{slash}SCT0_OUT8{slash}CTIMER_INP1{slash}CMP0_A)") (class "Default")
      (node (ref "TP3") (pin "1") (pinfunction "1_1") (pintype "passive"))
      (node (ref "U1") (pin "C1") (pinfunction "PIO2_14/SCT0_OUT8/CTIMER_INP1/CMP0_A_C1") (pintype "passive"))
    )
    (net (code "89") (name "Net-(U1E-PIO0_19{slash}FC2_SSEL2{slash}SCT0_GPI4{slash}SCT0_OUT4{slash}CTIMER_INP5{slash}UTICK_CAP0{slash}SEC_PIO0_19{slash}ADC0_2)") (class "Default")
      (node (ref "TP4") (pin "1") (pinfunction "1_1") (pintype "passive"))
      (node (ref "U1") (pin "A1") (pinfunction "PIO0_19/FC2_SSEL2/SCT0_GPI4/SCT0_OUT4/CTIMER_INP5/UTICK_CAP0/SEC_PIO0_19/ADC0_2_A1") (pintype "passive"))
    )
    (net (code "90") (name "Net-(U1E-PIO0_26{slash}FC3_SSEL2{slash}SCT0_GPI6{slash}SCT0_OUT6{slash}CTIMER_INP7{slash}SEC_PIO0_26{slash}ADC0_3)") (class "Default")
      (node (ref "TP5") (pin "1") (pinfunction "1_1") (pintype "passive"))
      (node (ref "U1") (pin "A2") (pinfunction "PIO0_26/FC3_SSEL2/SCT0_GPI6/SCT0_OUT6/CTIMER_INP7/SEC_PIO0_26/ADC0_3_A2") (pintype "passive"))
    )
    (net (code "91") (name "Net-(U1H-XTALIN)") (class "Default")
      (node (ref "C11") (pin "2") (pinfunction "1_2") (pintype "passive"))
      (node (ref "U1") (pin "B14") (pinfunction "XTALIN_B14") (pintype "input"))
      (node (ref "U5") (pin "2") (pinfunction "OSC2_2") (pintype "passive"))
    )
    (net (code "92") (name "Net-(U1H-XTALOUT)") (class "Default")
      (node (ref "C19") (pin "2") (pinfunction "1_2") (pintype "passive"))
      (node (ref "U1") (pin "B13") (pinfunction "XTALOUT_B13") (pintype "output"))
      (node (ref "U5") (pin "1") (pinfunction "OSC1_1") (pintype "passive"))
    )
    (net (code "93") (name "Net-(U2-ASYS)") (class "Default")
      (node (ref "C2") (pin "1") (pinfunction "1_1") (pintype "passive"))
      (node (ref "C5") (pin "1") (pinfunction "1_1") (pintype "passive"))
      (node (ref "C8") (pin "1") (pinfunction "1_1") (pintype "passive"))
      (node (ref "U2") (pin "17") (pinfunction "ASYS_17") (pintype "power_in"))
      (node (ref "U2") (pin "2") (pinfunction "PSYS2_2") (pintype "power_in"))
      (node (ref "U2") (pin "20") (pinfunction "PSYS1_20") (pintype "power_in"))
    )
    (net (code "94") (name "Net-(U2-LX1)") (class "Default")
      (node (ref "L2") (pin "1") (pinfunction "1_1") (pintype "passive"))
      (node (ref "U2") (pin "22") (pinfunction "LX1_22") (pintype "power_in"))
    )
    (net (code "95") (name "Net-(U2-LX2)") (class "Default")
      (node (ref "L3") (pin "1") (pinfunction "1_1") (pintype "passive"))
      (node (ref "U2") (pin "1") (pinfunction "LX2_1") (pintype "power_in"))
    )
    (net (code "96") (name "Net-(U2-SW1_OUT)") (class "Default")
      (node (ref "C7") (pin "2") (pinfunction "1_2") (pintype "passive"))
      (node (ref "L2") (pin "2") (pinfunction "2_2") (pintype "passive"))
      (node (ref "R7") (pin "1") (pinfunction "1_1") (pintype "passive"))
      (node (ref "U2") (pin "19") (pinfunction "SW1_OUT_19") (pintype "input"))
    )
    (net (code "97") (name "Net-(U2-SW2_OUT)") (class "Default")
      (node (ref "C9") (pin "2") (pinfunction "1_2") (pintype "passive"))
      (node (ref "L3") (pin "2") (pinfunction "2_2") (pintype "passive"))
      (node (ref "R10") (pin "1") (pinfunction "1_1") (pintype "passive"))
      (node (ref "U2") (pin "3") (pinfunction "SW2_OUT_3") (pintype "input"))
    )
    (net (code "98") (name "Net-(U7-LEDK)") (class "Default")
      (node (ref "R15") (pin "2") (pinfunction "2_2") (pintype "passive"))
      (node (ref "U7") (pin "2") (pinfunction "LEDK_2") (pintype "passive"))
    )
    (net (code "99") (name "VDD_CORE") (class "Default")
      (node (ref "C26") (pin "2") (pinfunction "2_2") (pintype "passive"))
      (node (ref "C27") (pin "2") (pinfunction "2_2") (pintype "passive"))
      (node (ref "C28") (pin "2") (pinfunction "2_2") (pintype "passive"))
      (node (ref "C29") (pin "2") (pinfunction "2_2") (pintype "passive"))
      (node (ref "C30") (pin "2") (pinfunction "2_2") (pintype "passive"))
      (node (ref "C31") (pin "2") (pinfunction "2_2") (pintype "passive"))
      (node (ref "C32") (pin "2") (pinfunction "2_2") (pintype "passive"))
      (node (ref "C33") (pin "2") (pinfunction "2_2") (pintype "passive"))
      (node (ref "C34") (pin "2") (pinfunction "2_2") (pintype "passive"))
      (node (ref "C35") (pin "2") (pinfunction "2_2") (pintype "passive"))
      (node (ref "R7") (pin "2") (pinfunction "2_2") (pintype "passive"))
      (node (ref "U1") (pin "C5") (pinfunction "VDDCORE_C5") (pintype "power_in"))
      (node (ref "U1") (pin "D9") (pinfunction "VDDCORE_D9") (pintype "power_in"))
      (node (ref "U1") (pin "F14") (pinfunction "VDDCORE_F14") (pintype "power_in"))
      (node (ref "U1") (pin "J14") (pinfunction "VDDCORE_J14") (pintype "power_in"))
      (node (ref "U1") (pin "J4") (pinfunction "VDDCORE_J4") (pintype "power_in"))
      (node (ref "U1") (pin "P9") (pinfunction "VDDCORE_P9") (pintype "power_in"))
      (node (ref "U1") (pin "R14") (pinfunction "VDDCORE_R14") (pintype "power_in"))
      (node (ref "U1") (pin "R5") (pinfunction "VDDCORE_R5") (pintype "power_in"))
    )
    (net (code "100") (name "unconnected-(J3-KEY-Pad7)") (class "Default")
      (node (ref "J3") (pin "7") (pinfunction "KEY_7") (pintype "passive+no_connect"))
    )
    (net (code "101") (name "unconnected-(J3-TDI-Pad8)") (class "Default")
      (node (ref "J3") (pin "8") (pinfunction "TDI_8") (pintype "passive+no_connect"))
    )
    (net (code "102") (name "unconnected-(U1D-PIO0_0{slash}FC0_SCK{slash}CTIMER0_MAT0{slash}I2S_BRIDGE_CLK_IN{slash}GPIO_INT_BMAT{slash}SEC_PIO0_0-PadG1)") (class "Default")
      (node (ref "U1") (pin "G1") (pinfunction "PIO0_0/FC0_SCK/CTIMER0_MAT0/I2S_BRIDGE_CLK_IN/GPIO_INT_BMAT/SEC_PIO0_0_G1") (pintype "passive+no_connect"))
    )
    (net (code "103") (name "unconnected-(U1D-PIO0_3{slash}FC0_CTS_SDA_SSEL0{slash}CTIMER0_MAT3{slash}FC1_SSEL2{slash}SEC_PIO0_3-PadH2)") (class "Default")
      (node (ref "U1") (pin "H2") (pinfunction "PIO0_3/FC0_CTS_SDA_SSEL0/CTIMER0_MAT3/FC1_SSEL2/SEC_PIO0_3_H2") (pintype "passive+no_connect"))
    )
    (net (code "104") (name "unconnected-(U1D-PIO0_7{slash}FC1_SCK{slash}SCT0_GPI4{slash}SCT0_OUT4{slash}CTIMER1_MAT0{slash}I2S_BRIDGE_CLK_OUT{slash}SEC_PIO0_7-PadJ2)") (class "Default")
      (node (ref "U1") (pin "J2") (pinfunction "PIO0_7/FC1_SCK/SCT0_GPI4/SCT0_OUT4/CTIMER1_MAT0/I2S_BRIDGE_CLK_OUT/SEC_PIO0_7_J2") (pintype "passive+no_connect"))
    )
    (net (code "105") (name "unconnected-(U1D-PIO0_8{slash}FC1_TXD_SCL_MISO_WS{slash}SCT0_GPI5{slash}SCT0_OUT5{slash}CTIMER1_MAT1{slash}I2S_BRIDGE_WS_OUT{slash}SEC_PIO0_8-PadK4)") (class "Default")
      (node (ref "U1") (pin "K4") (pinfunction "PIO0_8/FC1_TXD_SCL_MISO_WS/SCT0_GPI5/SCT0_OUT5/CTIMER1_MAT1/I2S_BRIDGE_WS_OUT/SEC_PIO0_8_K4") (pintype "passive+no_connect"))
    )
    (net (code "106") (name "unconnected-(U1D-PIO0_9{slash}FC1_RXD_SDA_MOSI_DATA{slash}SCT0_GPI6{slash}SCT0_OUT6{slash}CTIMER1_MAT2{slash}I2S_BRIDGE_DATA_OUT{slash}SEC_PIO0_9-PadL3)") (class "Default")
      (node (ref "U1") (pin "L3") (pinfunction "PIO0_9/FC1_RXD_SDA_MOSI_DATA/SCT0_GPI6/SCT0_OUT6/CTIMER1_MAT2/I2S_BRIDGE_DATA_OUT/SEC_PIO0_9_L3") (pintype "passive+no_connect"))
    )
    (net (code "107") (name "unconnected-(U1D-PIO0_10{slash}FC1_CTS_SDA_SSEL0{slash}SCT0_GPI7{slash}SCT0_OUT7{slash}CTIMER1_MAT3{slash}FC0_SSEL2{slash}SEC_PIO0_10-PadJ3)") (class "Default")
      (node (ref "U1") (pin "J3") (pinfunction "PIO0_10/FC1_CTS_SDA_SSEL0/SCT0_GPI7/SCT0_OUT7/CTIMER1_MAT3/FC0_SSEL2/SEC_PIO0_10_J3") (pintype "passive+no_connect"))
    )
    (net (code "108") (name "unconnected-(U1D-PIO0_13{slash}FC1_SSEL3{slash}SCT0_GPI3{slash}SCT0_OUT3{slash}CTIMER0_MAT1{slash}SEC_PIO0_13{slash}ADC0_9-PadG3)") (class "Default")
      (node (ref "U1") (pin "G3") (pinfunction "PIO0_13/FC1_SSEL3/SCT0_GPI3/SCT0_OUT3/CTIMER0_MAT1/SEC_PIO0_13/ADC0_9_G3") (pintype "passive+no_connect"))
    )
    (net (code "109") (name "unconnected-(U1D-PIO1_24{slash}FLEXSPI0A_DATA4{slash}SCT0_GPI3-PadT7)") (class "Default")
      (node (ref "U1") (pin "T7") (pinfunction "PIO1_24/FLEXSPI0A_DATA4/SCT0_GPI3_T7") (pintype "passive+no_connect"))
    )
    (net (code "110") (name "unconnected-(U1D-PIO1_25{slash}FLEXSPI0A_DATA5{slash}SCT0_OUT3-PadU7)") (class "Default")
      (node (ref "U1") (pin "U7") (pinfunction "PIO1_25/FLEXSPI0A_DATA5/SCT0_OUT3_U7") (pintype "passive+no_connect"))
    )
    (net (code "111") (name "unconnected-(U1D-PIO1_26{slash}FLEXSPI0A_DATA6{slash}SCT0_GPI4-PadR7)") (class "Default")
      (node (ref "U1") (pin "R7") (pinfunction "PIO1_26/FLEXSPI0A_DATA6/SCT0_GPI4_R7") (pintype "passive+no_connect"))
    )
    (net (code "112") (name "unconnected-(U1D-PIO1_27{slash}FLEXSPI0A_DATA7{slash}SCT0_OUT4-PadT8)") (class "Default")
      (node (ref "U1") (pin "T8") (pinfunction "PIO1_27/FLEXSPI0A_DATA7/SCT0_OUT4_T8") (pintype "passive+no_connect"))
    )
    (net (code "113") (name "unconnected-(U1D-PIO1_28{slash}FLEXSPI0A_DQS{slash}SCT0_GPI5-PadU9)") (class "Default")
      (node (ref "U1") (pin "U9") (pinfunction "PIO1_28/FLEXSPI0A_DQS/SCT0_GPI5_U9") (pintype "passive+no_connect"))
    )
    (net (code "114") (name "unconnected-(U1D-PIO1_29{slash}FLEXSPI0A_SS1_N{slash}SCT0_OUT5{slash}UTICK_CAP2{slash}CTIMER_INP13{slash}FLEXSPI0B_SCLK-PadU3)") (class "Default")
      (node (ref "U1") (pin "U3") (pinfunction "PIO1_29/FLEXSPI0A_SS1_N/SCT0_OUT5/UTICK_CAP2/CTIMER_INP13/FLEXSPI0B_SCLK_U3") (pintype "passive+no_connect"))
    )
    (net (code "115") (name "unconnected-(U1D-PIO2_12{slash}SCT0_OUT6{slash}CTIMER2_MAT2-PadT3)") (class "Default")
      (node (ref "U1") (pin "T3") (pinfunction "PIO2_12/SCT0_OUT6/CTIMER2_MAT2_T3") (pintype "passive+no_connect"))
    )
    (net (code "116") (name "unconnected-(U1D-PIO2_13{slash}SCT0_OUT7{slash}CTIMER2_MAT3{slash}CMP0_OUT-PadT1)") (class "Default")
      (node (ref "U1") (pin "T1") (pinfunction "PIO2_13/SCT0_OUT7/CTIMER2_MAT3/CMP0_OUT_T1") (pintype "passive+no_connect"))
    )
    (net (code "117") (name "unconnected-(U1D-PIO2_15{slash}SCT0_OUT9{slash}CLKIN{slash}CMP0_D-PadE2)") (class "Default")
      (node (ref "U1") (pin "E2") (pinfunction "PIO2_15/SCT0_OUT9/CLKIN/CMP0_D_E2") (pintype "passive+no_connect"))
    )
    (net (code "118") (name "unconnected-(U1E-PIO0_17{slash}FC2_CTS_SDA_SSEL0{slash}SCT0_GPI3{slash}SCT0_OUT3{slash}CTIMER2_MAT3{slash}FC5_SSEL2{slash}SEC_PIO0_17-PadD7)") (class "Default")
      (node (ref "U1") (pin "D7") (pinfunction "PIO0_17/FC2_CTS_SDA_SSEL0/SCT0_GPI3/SCT0_OUT3/CTIMER2_MAT3/FC5_SSEL2/SEC_PIO0_17_D7") (pintype "passive+no_connect"))
    )
    (net (code "119") (name "unconnected-(U1E-PIO0_18{slash}FC2_RTS_SCL_SSEL1{slash}SCT0_GPI6{slash}SCT0_OUT6{slash}CTIMER_INP4{slash}FC5_SSEL3{slash}SEC_PIO0_18-PadB7)") (class "Default")
      (node (ref "U1") (pin "B7") (pinfunction "PIO0_18/FC2_RTS_SCL_SSEL1/SCT0_GPI6/SCT0_OUT6/CTIMER_INP4/FC5_SSEL3/SEC_PIO0_18_B7") (pintype "passive+no_connect"))
    )
    (net (code "120") (name "unconnected-(U1E-PIO0_20{slash}FC2_SSEL3{slash}SCT0_GPI5{slash}SCT0_OUT5{slash}CTIMER0_MAT2{slash}CTIMER_INP11{slash}SEC_PIO0_20{slash}ADC0_10-PadB2)") (class "Default")
      (node (ref "U1") (pin "B2") (pinfunction "PIO0_20/FC2_SSEL3/SCT0_GPI5/SCT0_OUT5/CTIMER0_MAT2/CTIMER_INP11/SEC_PIO0_20/ADC0_10_B2") (pintype "passive+no_connect"))
    )
    (net (code "121") (name "unconnected-(U1E-PIO0_24{slash}FC3_CTS_SDA_SSEL0{slash}CTIMER3_MAT3{slash}FC2_SSEL2{slash}TRACEDATA(2){slash}CLKOUT{slash}SEC_PIO0_24-PadB9)") (class "Default")
      (node (ref "U1") (pin "B9") (pinfunction "PIO0_24/FC3_CTS_SDA_SSEL0/CTIMER3_MAT3/FC2_SSEL2/TRACEDATA(2)/CLKOUT/SEC_PIO0_24_B9") (pintype "passive+no_connect"))
    )
    (net (code "122") (name "unconnected-(U1E-PIO0_25{slash}FC3_RTS_SCL_SSEL1{slash}FREQME_GPIO_CLK{slash}CTIMER_INP6{slash}FC2_SSEL3{slash}TRACEDATA(3){slash}CLKIN{slash}SEC_PIO0_25-PadA9)") (class "Default")
      (node (ref "U1") (pin "A9") (pinfunction "PIO0_25/FC3_RTS_SCL_SSEL1/FREQME_GPIO_CLK/CTIMER_INP6/FC2_SSEL3/TRACEDATA(3)/CLKIN/SEC_PIO0_25_A9") (pintype "passive+no_connect"))
    )
    (net (code "123") (name "unconnected-(U1E-PIO0_27{slash}FC3_SSEL3{slash}SCT0_GPI7{slash}SCT0_OUT7{slash}CTIMER0_MAT3{slash}SEC_PIO0_27{slash}ADC0_11-PadB3)") (class "Default")
      (node (ref "U1") (pin "B3") (pinfunction "PIO0_27/FC3_SSEL3/SCT0_GPI7/SCT0_OUT7/CTIMER0_MAT3/SEC_PIO0_27/ADC0_11_B3") (pintype "passive+no_connect"))
    )
    (net (code "124") (name "unconnected-(U1E-PIO0_31{slash}FC4_CTS_SDA_SSEL0{slash}SCT0_GPI0{slash}SCT0_OUT6{slash}CTIMER4_MAT3{slash}FC3_SSEL2{slash}SEC_PIO0_31-PadA11)") (class "Default")
      (node (ref "U1") (pin "A11") (pinfunction "PIO0_31/FC4_CTS_SDA_SSEL0/SCT0_GPI0/SCT0_OUT6/CTIMER4_MAT3/FC3_SSEL2/SEC_PIO0_31_A11") (pintype "passive+no_connect"))
    )
    (net (code "125") (name "unconnected-(U1E-PIO1_0{slash}FC4_RTS_SCL_SSEL1{slash}SCT0_GPI1{slash}SCT0_OUT7{slash}CTIMER_INP8{slash}FC3_SSEL3-PadE17)") (class "Default")
      (node (ref "U1") (pin "E17") (pinfunction "PIO1_0/FC4_RTS_SCL_SSEL1/SCT0_GPI1/SCT0_OUT7/CTIMER_INP8/FC3_SSEL3_E17") (pintype "passive+no_connect"))
    )
    (net (code "126") (name "unconnected-(U1E-PIO1_1{slash}FC4_SSEL2{slash}SCT0_GPI2{slash}SCT0_OUT8{slash}CTIMER1_MAT0-PadG15)") (class "Default")
      (node (ref "U1") (pin "G15") (pinfunction "PIO1_1/FC4_SSEL2/SCT0_GPI2/SCT0_OUT8/CTIMER1_MAT0_G15") (pintype "passive+no_connect"))
    )
    (net (code "127") (name "unconnected-(U1E-PIO1_2{slash}FC4_SSEL3{slash}SCT0_GPI3{slash}SCT0_OUT9{slash}CTIMER1_MAT1{slash}CMP0_C-PadA7)") (class "Default")
      (node (ref "U1") (pin "A7") (pinfunction "PIO1_2/FC4_SSEL3/SCT0_GPI3/SCT0_OUT9/CTIMER1_MAT1/CMP0_C_A7") (pintype "passive+no_connect"))
    )
    (net (code "128") (name "unconnected-(U1E-PIO1_7{slash}FC5_RTS_SCL_SSEL1{slash}SCT0_GPI5{slash}SCT0_OUT5{slash}CTIMER_INP9{slash}FC4_SSEL3-PadJ15)") (class "Default")
      (node (ref "U1") (pin "J15") (pinfunction "PIO1_7/FC5_RTS_SCL_SSEL1/SCT0_GPI5/SCT0_OUT5/CTIMER_INP9/FC4_SSEL3_J15") (pintype "passive+no_connect"))
    )
    (net (code "129") (name "unconnected-(U1E-PIO2_27{slash}USB1_OVERCURRENTN-PadM14)") (class "Default")
      (node (ref "U1") (pin "M14") (pinfunction "PIO2_27/USB1_OVERCURRENTN_M14") (pintype "passive+no_connect"))
    )
    (net (code "130") (name "unconnected-(U1E-PIO2_28{slash}USB1_PORTPWRN-PadN15)") (class "Default")
      (node (ref "U1") (pin "N15") (pinfunction "PIO2_28/USB1_PORTPWRN_N15") (pintype "passive+no_connect"))
    )
    (net (code "131") (name "unconnected-(U1F-PIO2_4{slash}SD0_WR_PRT{slash}SCT0_OUT2{slash}SD0_DS-PadT13)") (class "Default")
      (node (ref "U1") (pin "T13") (pinfunction "PIO2_4/SD0_WR_PRT/SCT0_OUT2/SD0_DS_T13") (pintype "passive+no_connect"))
    )
    (net (code "132") (name "unconnected-(U1F-PIO2_11{slash}SD0_VOLT{slash}SCT0_GPI7{slash}CTIMER2_MAT1-PadT16)") (class "Default")
      (node (ref "U1") (pin "T16") (pinfunction "PIO2_11/SD0_VOLT/SCT0_GPI7/CTIMER2_MAT1_T16") (pintype "passive+no_connect"))
    )
    (net (code "133") (name "unconnected-(U1H-RTCXIN-PadB17)") (class "Default")
      (node (ref "U1") (pin "B17") (pinfunction "RTCXIN_B17") (pintype "input+no_connect"))
    )
    (net (code "134") (name "unconnected-(U1H-RTCXOUT-PadA17)") (class "Default")
      (node (ref "U1") (pin "A17") (pinfunction "RTCXOUT_A17") (pintype "output+no_connect"))
    )
  )
)
